# axiom_beta_plugin_module_TE0714_SDI_v0_8.net
KiCad netlist of a schematic drawn in EAGLE
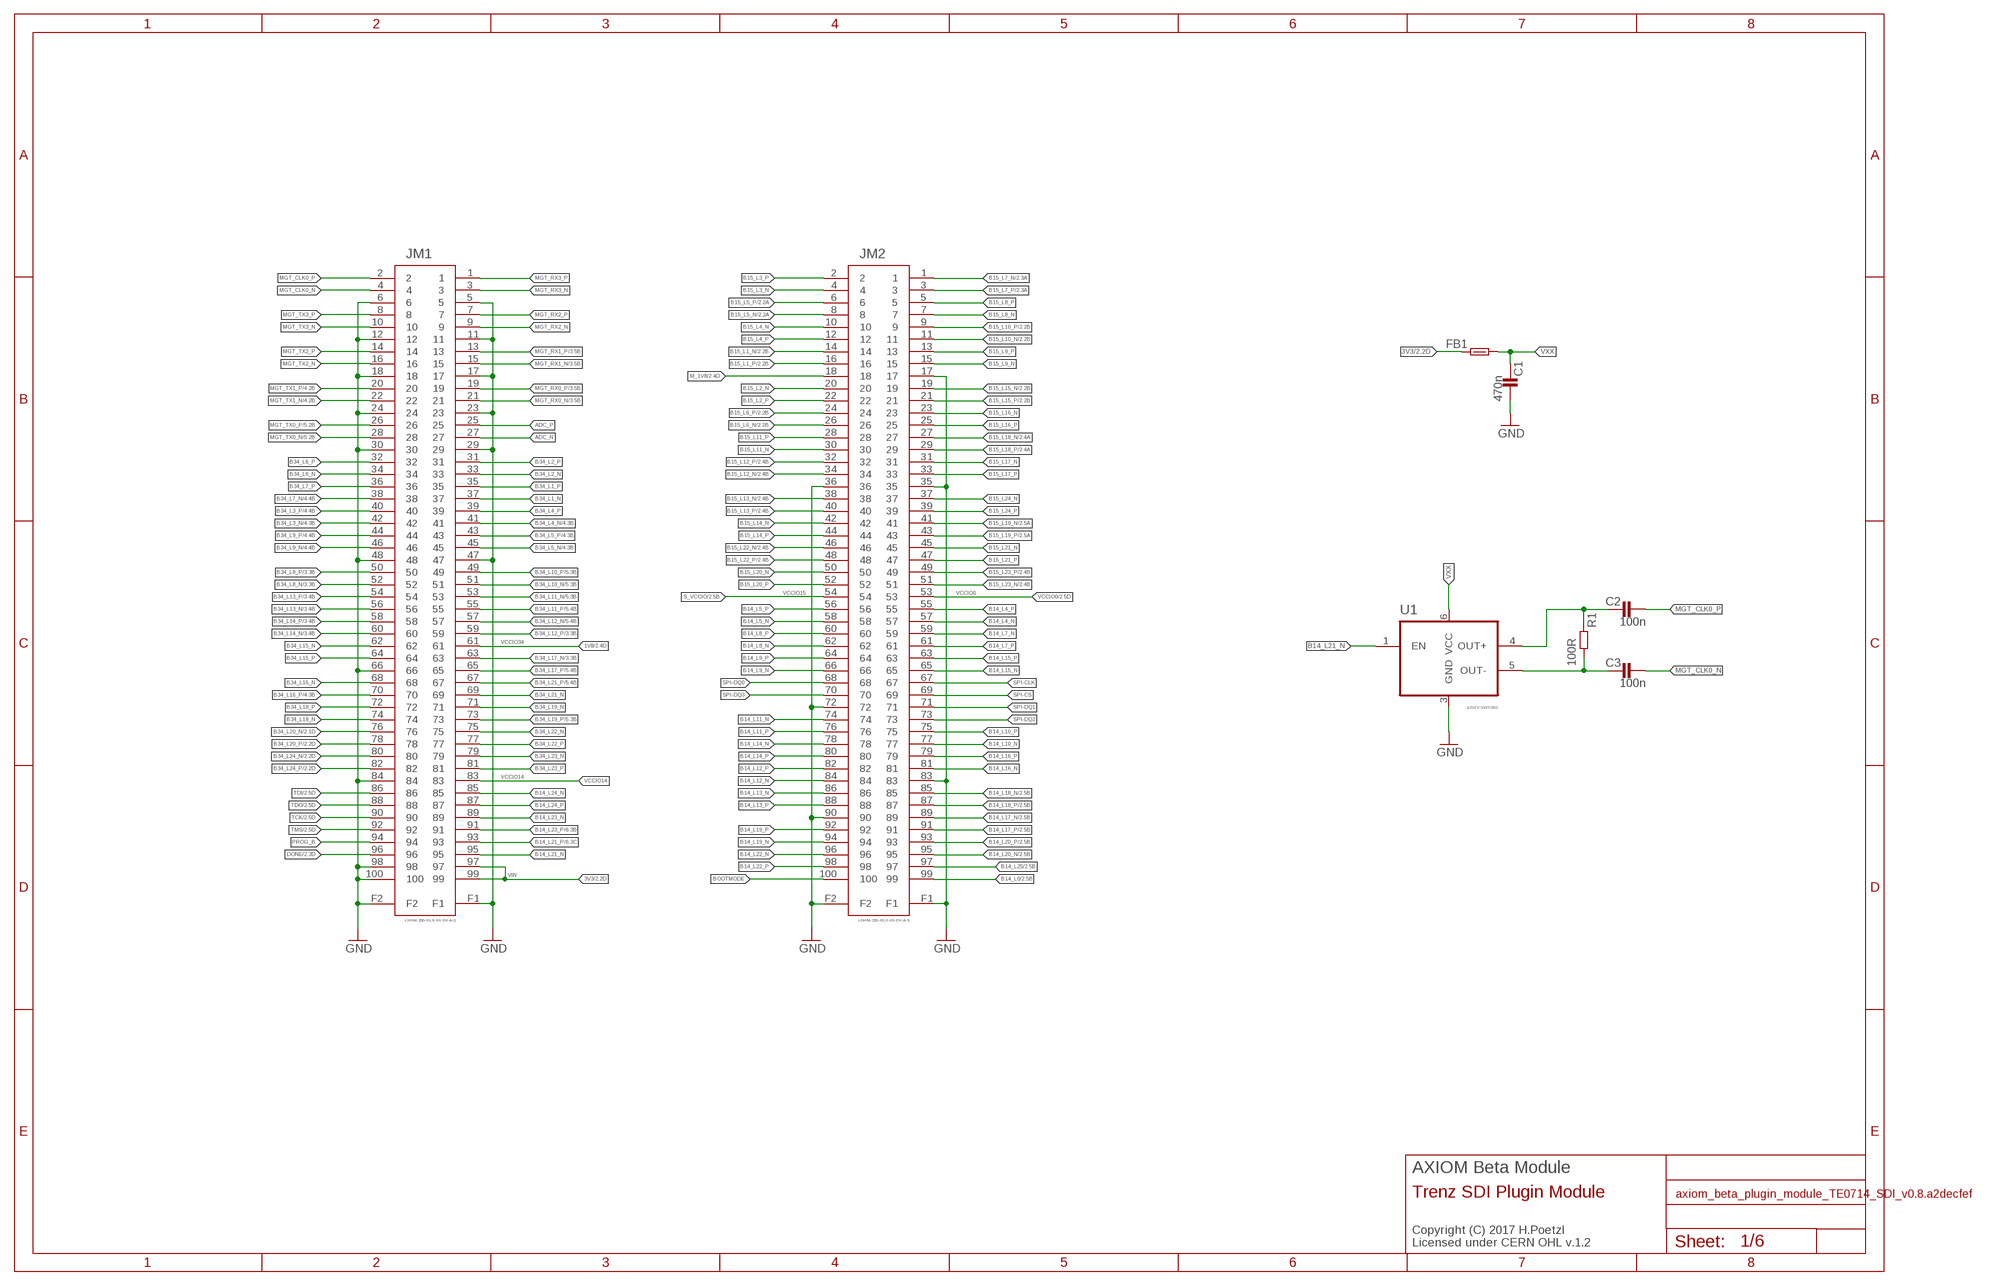
[diagram p0: schematic, sheet 1]
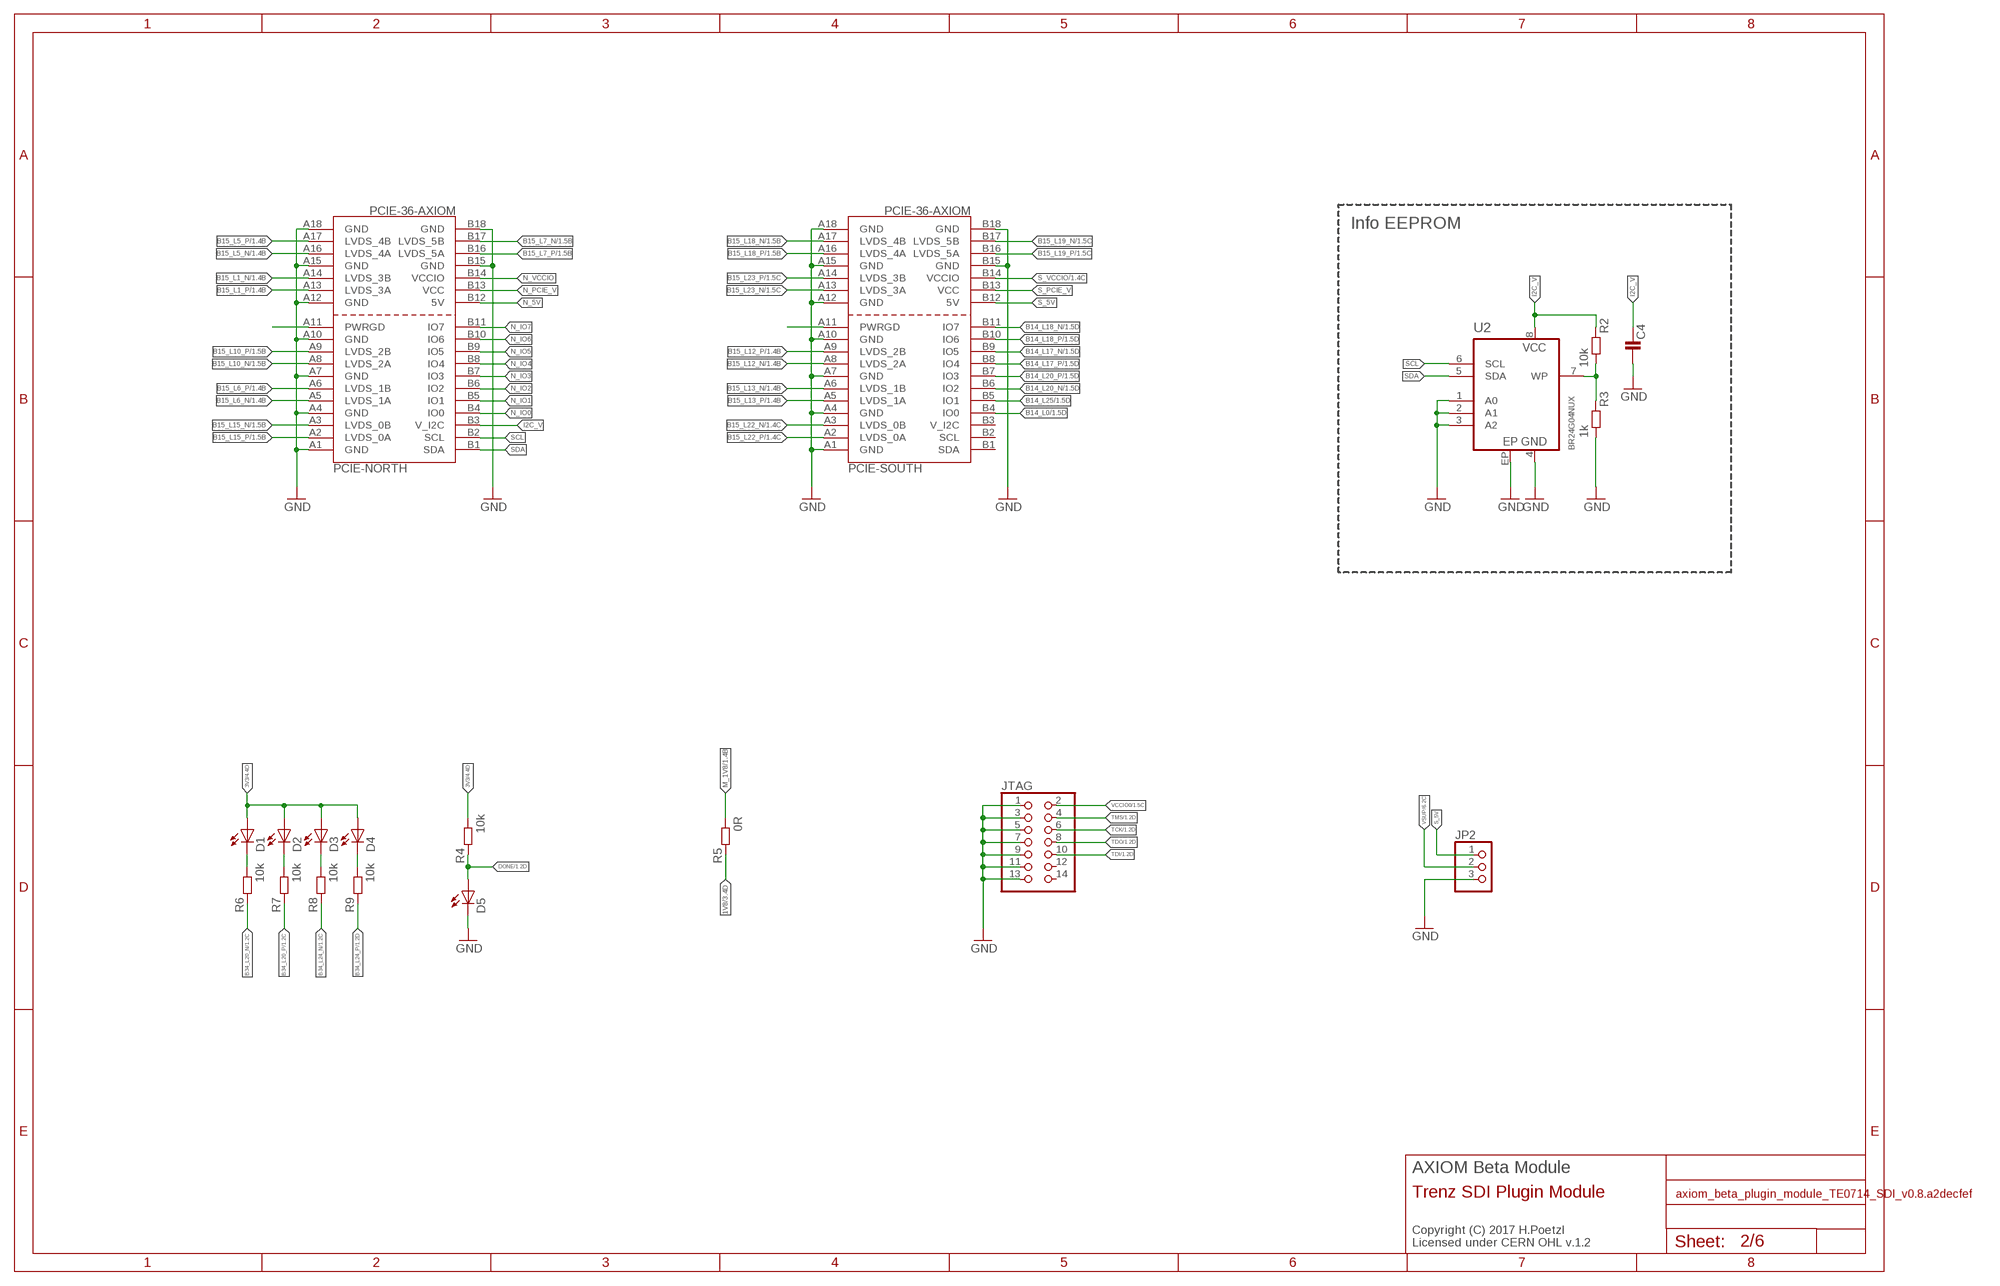
[diagram p1: schematic, sheet 2]
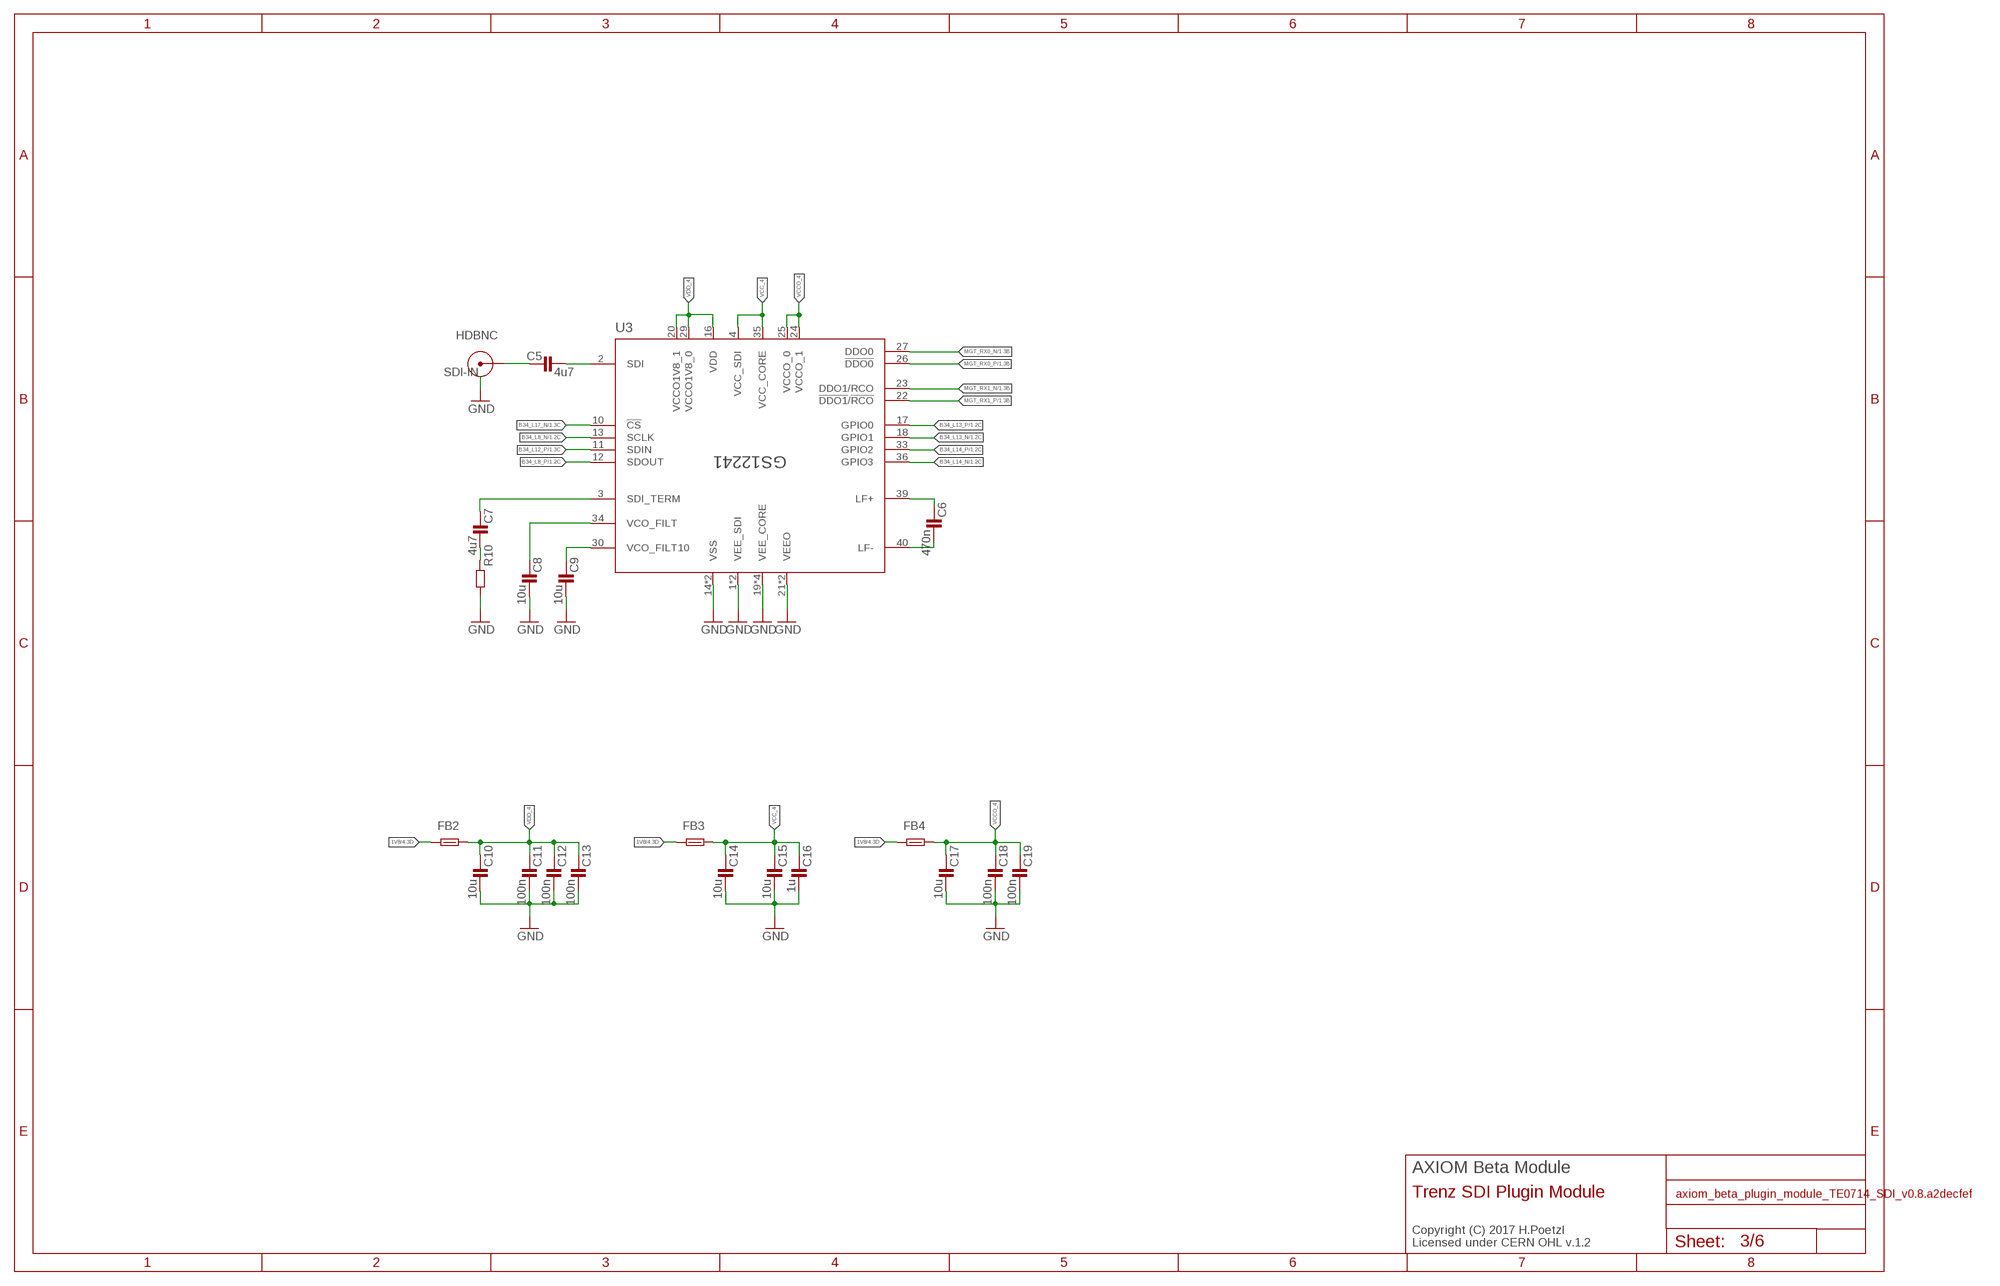
[diagram p2: schematic, sheet 3]
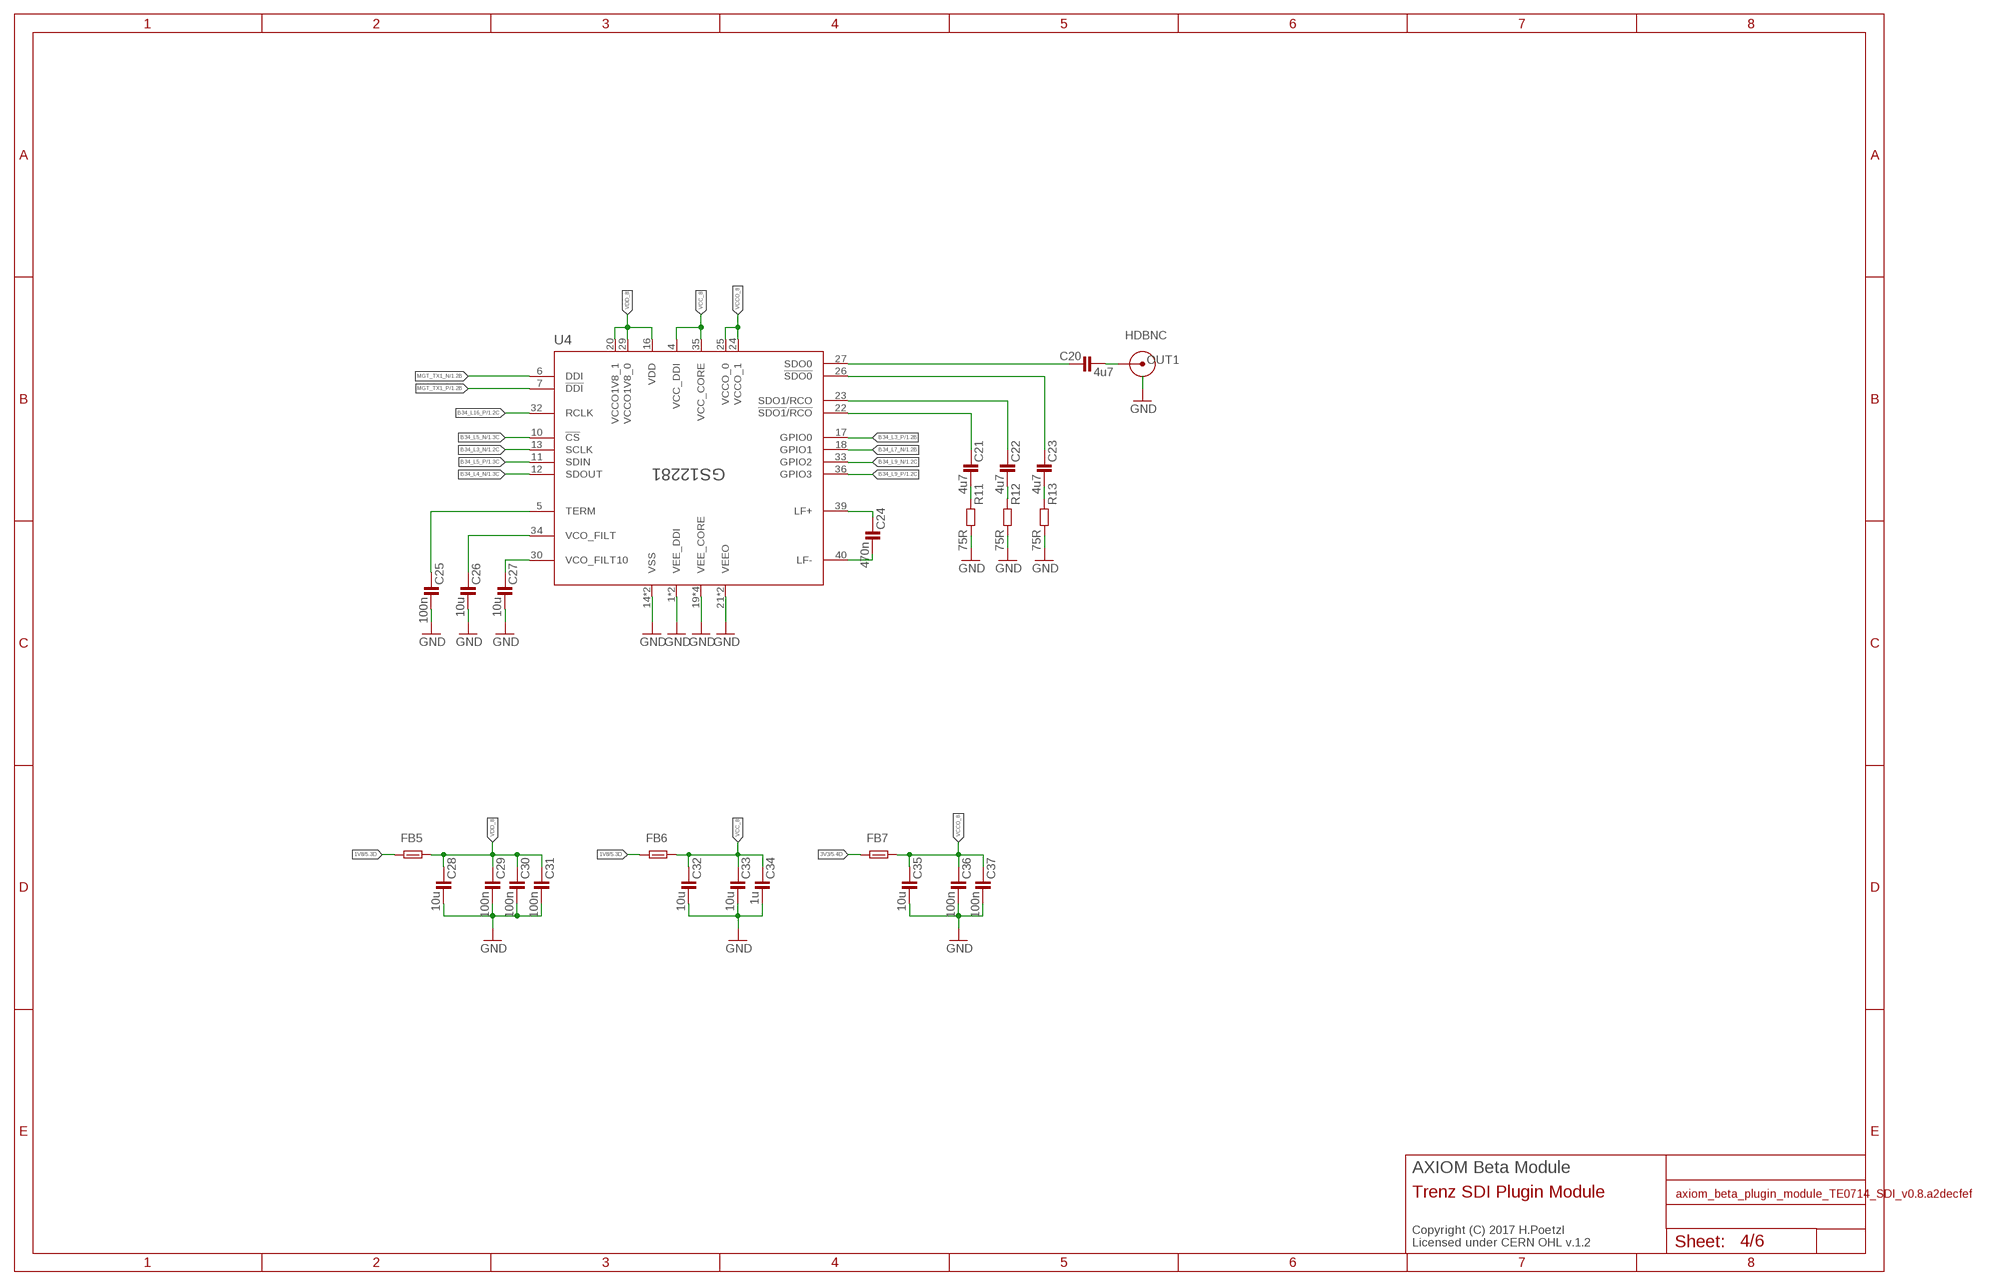
[diagram p3: schematic, sheet 4]
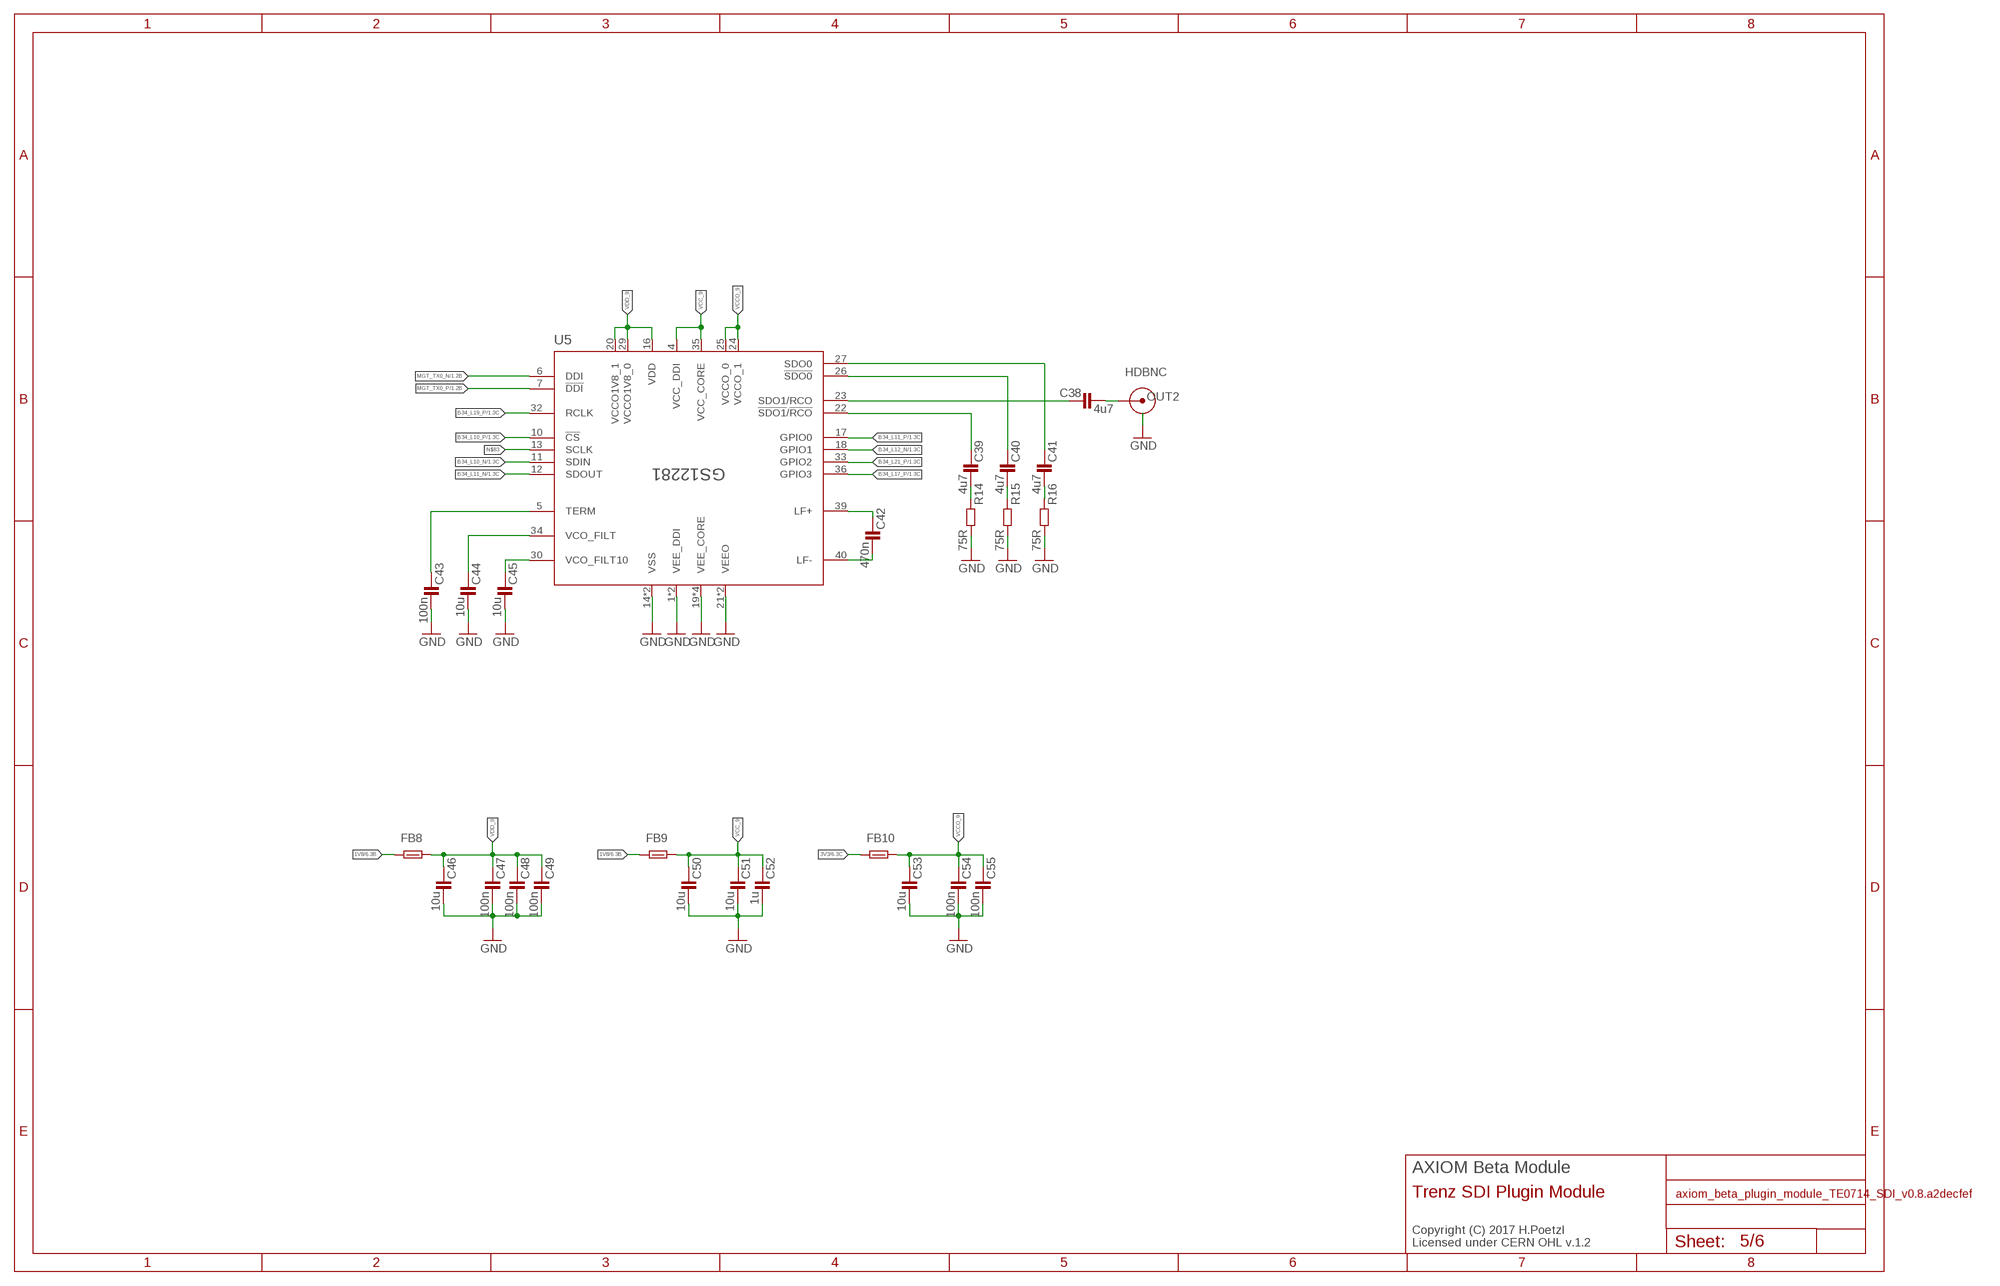
[diagram p4: schematic, sheet 5]
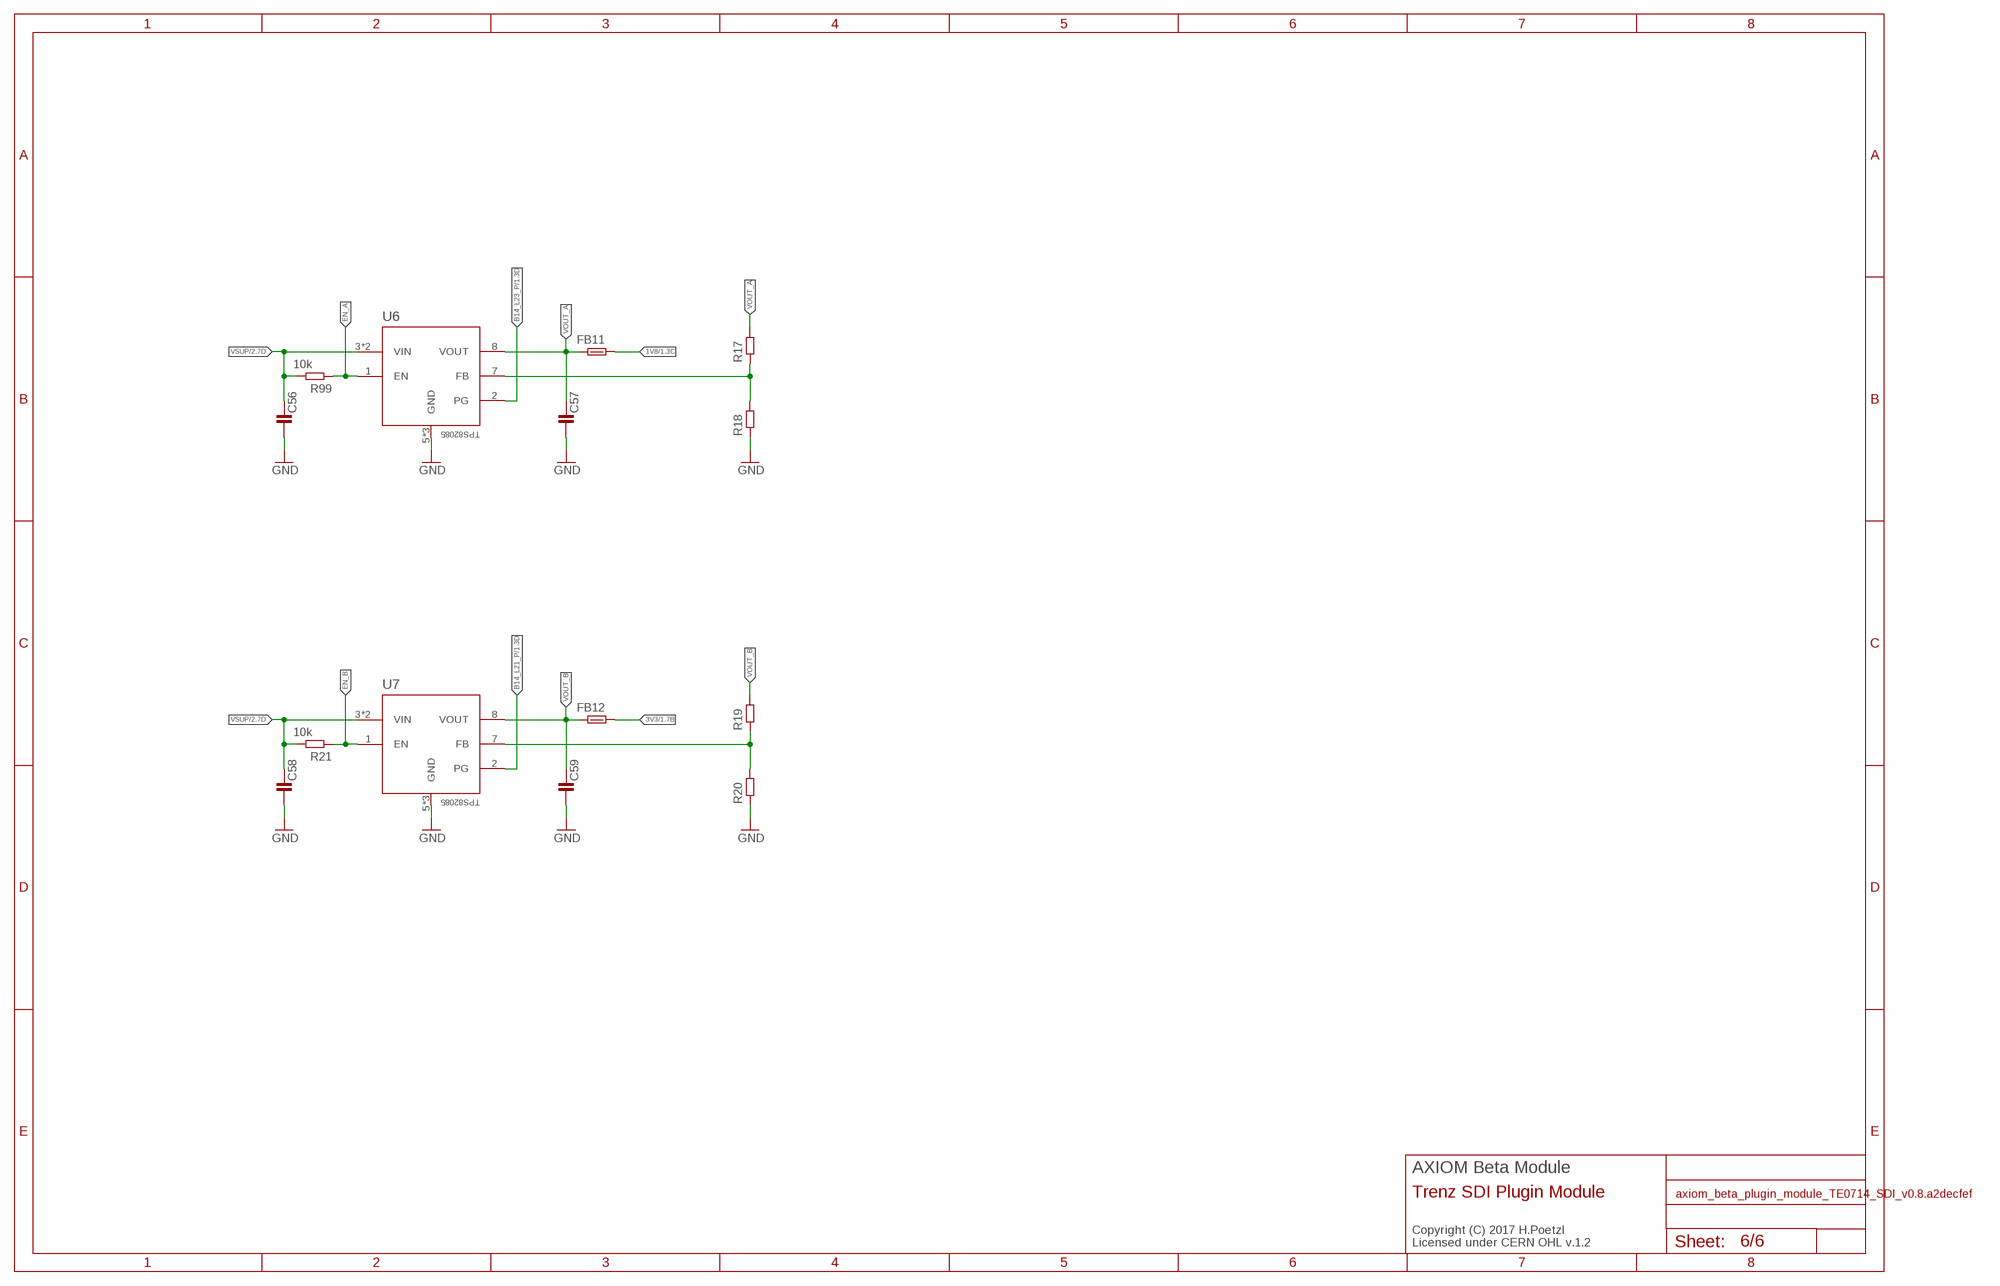
[diagram p5: schematic, sheet 6]

(export (version "E")
  (design (tool "Eeschema 10.0.6"))
  (components
    (comp (ref "C1")
      (value "470n")
      (footprint "eagle-import:0402-C")
      (libsource (lib "eagle-import") (part "C0402-C"))
    )
    (comp (ref "C2")
      (value "100n")
      (footprint "eagle-import:0201-C")
      (libsource (lib "eagle-import") (part "C0201-C"))
    )
    (comp (ref "C3")
      (value "100n")
      (footprint "eagle-import:0201-C")
      (libsource (lib "eagle-import") (part "C0201-C"))
    )
    (comp (ref "FB1")
      (value "FB0402-C")
      (footprint "eagle-import:0402-C")
      (libsource (lib "eagle-import") (part "FB0402-C"))
    )
    (comp (ref "JM1")
      (value "LSHM-150-XX.X-XX-DV-A-S")
      (footprint "eagle-import:LSHM-150-XX.X-XX-DV-A-S")
      (libsource (lib "eagle-import") (part "LSHM-150-XX.X-XX-DV-A-S"))
    )
    (comp (ref "JM2")
      (value "LSHM-150-XX.X-XX-DV-A-S")
      (footprint "eagle-import:LSHM-150-XX.X-XX-DV-A-S")
      (libsource (lib "eagle-import") (part "LSHM-150-XX.X-XX-DV-A-S"))
    )
    (comp (ref "R1")
      (value "100R")
      (footprint "eagle-import:0201-C")
      (libsource (lib "eagle-import") (part "R0201-C"))
    )
    (comp (ref "U1")
      (value "DSC11XX-3.2X2.5")
      (footprint "eagle-import:3.2X2.5")
      (libsource (lib "eagle-import") (part "DSC11XX-3.2X2.5"))
    )
    (comp (ref "C5")
      (value "4u7")
      (footprint "eagle-import:0402-C")
      (libsource (lib "eagle-import") (part "C0402-C"))
    )
    (comp (ref "C6")
      (value "470n")
      (footprint "eagle-import:0201-C")
      (libsource (lib "eagle-import") (part "C0201-C"))
    )
    (comp (ref "C7")
      (value "4u7")
      (footprint "eagle-import:0402-C")
      (libsource (lib "eagle-import") (part "C0402-C"))
    )
    (comp (ref "C8")
      (value "10u")
      (footprint "eagle-import:0201-C")
      (libsource (lib "eagle-import") (part "C0201-C"))
    )
    (comp (ref "C9")
      (value "10u")
      (footprint "eagle-import:0402-C")
      (libsource (lib "eagle-import") (part "C0402-C"))
    )
    (comp (ref "C10")
      (value "10u")
      (footprint "eagle-import:0402-C")
      (libsource (lib "eagle-import") (part "C0402-C"))
    )
    (comp (ref "C11")
      (value "100n")
      (footprint "eagle-import:0201-C")
      (libsource (lib "eagle-import") (part "C0201-C"))
    )
    (comp (ref "C12")
      (value "100n")
      (footprint "eagle-import:0201-C")
      (libsource (lib "eagle-import") (part "C0201-C"))
    )
    (comp (ref "C13")
      (value "100n")
      (footprint "eagle-import:0201-C")
      (libsource (lib "eagle-import") (part "C0201-C"))
    )
    (comp (ref "C14")
      (value "10u")
      (footprint "eagle-import:0402-C")
      (libsource (lib "eagle-import") (part "C0402-C"))
    )
    (comp (ref "C15")
      (value "10u")
      (footprint "eagle-import:0402-C")
      (libsource (lib "eagle-import") (part "C0402-C"))
    )
    (comp (ref "C16")
      (value "1u")
      (footprint "eagle-import:0201-C")
      (libsource (lib "eagle-import") (part "C0201-C"))
    )
    (comp (ref "C17")
      (value "10u")
      (footprint "eagle-import:0402-C")
      (libsource (lib "eagle-import") (part "C0402-C"))
    )
    (comp (ref "C18")
      (value "100n")
      (footprint "eagle-import:0201-C")
      (libsource (lib "eagle-import") (part "C0201-C"))
    )
    (comp (ref "C19")
      (value "100n")
      (footprint "eagle-import:0201-C")
      (libsource (lib "eagle-import") (part "C0201-C"))
    )
    (comp (ref "FB2")
      (value "FB0402-C")
      (footprint "eagle-import:0402-C")
      (libsource (lib "eagle-import") (part "FB0402-C"))
    )
    (comp (ref "FB3")
      (value "FB0402-C")
      (footprint "eagle-import:0402-C")
      (libsource (lib "eagle-import") (part "FB0402-C"))
    )
    (comp (ref "FB4")
      (value "FB0402-C")
      (footprint "eagle-import:0402-C")
      (libsource (lib "eagle-import") (part "FB0402-C"))
    )
    (comp (ref "R10")
      (value "R0201-C")
      (footprint "eagle-import:0201-C")
      (libsource (lib "eagle-import") (part "R0201-C"))
    )
    (comp (ref "SDI-IN")
      (value "HDBNC")
      (footprint "eagle-import:HDBNC_EDGE_2SIDE")
      (libsource (lib "eagle-import") (part "HDBNC"))
    )
    (comp (ref "U3")
      (value "GS12241")
      (footprint "eagle-import:UQFN40P600X400X100-41N")
      (libsource (lib "eagle-import") (part "GS12241"))
    )
    (comp (ref "C4")
      (value "C0402-B")
      (footprint "eagle-import:0402-B")
      (libsource (lib "eagle-import") (part "C0402-B"))
    )
    (comp (ref "D1")
      (value "LED")
      (footprint "eagle-import:CHIPLED_0603")
      (libsource (lib "eagle-import") (part "LED"))
    )
    (comp (ref "D2")
      (value "LED")
      (footprint "eagle-import:CHIPLED_0603")
      (libsource (lib "eagle-import") (part "LED"))
    )
    (comp (ref "D3")
      (value "LED")
      (footprint "eagle-import:CHIPLED_0603")
      (libsource (lib "eagle-import") (part "LED"))
    )
    (comp (ref "D4")
      (value "LED")
      (footprint "eagle-import:CHIPLED_0603")
      (libsource (lib "eagle-import") (part "LED"))
    )
    (comp (ref "D5")
      (value "LED")
      (footprint "eagle-import:CHIPLED_0603")
      (libsource (lib "eagle-import") (part "LED"))
    )
    (comp (ref "JP2")
      (value "PINHD-1X03_2.54-90°-S")
      (footprint "eagle-import:1X03_90-S")
      (libsource (lib "eagle-import") (part "PINHD-1X03_2.54-90°-S"))
    )
    (comp (ref "JTAG")
      (value "PINHD-2X07_2.00")
      (footprint "eagle-import:2X07M")
      (libsource (lib "eagle-import") (part "PINHD-2X07_2.00"))
    )
    (comp (ref "PCIE-NORTH")
      (value "PCIE-36-AXIOM")
      (footprint "eagle-import:PCIE-36-AXIOM")
      (libsource (lib "eagle-import") (part "PCIE-36-AXIOM"))
    )
    (comp (ref "PCIE-SOUTH")
      (value "PCIE-36-AXIOM")
      (footprint "eagle-import:PCIE-36-AXIOM")
      (libsource (lib "eagle-import") (part "PCIE-36-AXIOM"))
    )
    (comp (ref "R2")
      (value "10k")
      (footprint "eagle-import:0402-B")
      (libsource (lib "eagle-import") (part "R0402-B"))
    )
    (comp (ref "R3")
      (value "1k")
      (footprint "eagle-import:0402-B")
      (libsource (lib "eagle-import") (part "R0402-B"))
    )
    (comp (ref "R4")
      (value "10k")
      (footprint "eagle-import:0402-C")
      (libsource (lib "eagle-import") (part "R0402-C"))
    )
    (comp (ref "R5")
      (value "0R")
      (footprint "eagle-import:0402-C")
      (libsource (lib "eagle-import") (part "R0402-C"))
    )
    (comp (ref "R6")
      (value "10k")
      (footprint "eagle-import:0402-C")
      (libsource (lib "eagle-import") (part "R0402-C"))
    )
    (comp (ref "R7")
      (value "10k")
      (footprint "eagle-import:0402-C")
      (libsource (lib "eagle-import") (part "R0402-C"))
    )
    (comp (ref "R8")
      (value "10k")
      (footprint "eagle-import:0402-C")
      (libsource (lib "eagle-import") (part "R0402-C"))
    )
    (comp (ref "R9")
      (value "10k")
      (footprint "eagle-import:0402-C")
      (libsource (lib "eagle-import") (part "R0402-C"))
    )
    (comp (ref "U2")
      (value "BR24G04NUX")
      (footprint "eagle-import:DFN200X300X100-9N")
      (libsource (lib "eagle-import") (part "BR24G04NUX"))
    )
    (comp (ref "C56")
      (value "C0603-C")
      (footprint "eagle-import:0603-C")
      (libsource (lib "eagle-import") (part "C0603-C"))
    )
    (comp (ref "C57")
      (value "C0603-C")
      (footprint "eagle-import:0603-C")
      (libsource (lib "eagle-import") (part "C0603-C"))
    )
    (comp (ref "C58")
      (value "C0603-C")
      (footprint "eagle-import:0603-C")
      (libsource (lib "eagle-import") (part "C0603-C"))
    )
    (comp (ref "C59")
      (value "C0603-C")
      (footprint "eagle-import:0603-C")
      (libsource (lib "eagle-import") (part "C0603-C"))
    )
    (comp (ref "FB11")
      (value "FB0603-C")
      (footprint "eagle-import:0603-C")
      (libsource (lib "eagle-import") (part "FB0603-C"))
    )
    (comp (ref "FB12")
      (value "FB0603-C")
      (footprint "eagle-import:0603-C")
      (libsource (lib "eagle-import") (part "FB0603-C"))
    )
    (comp (ref "R17")
      (value "R0201-C")
      (footprint "eagle-import:0201-C")
      (libsource (lib "eagle-import") (part "R0201-C"))
    )
    (comp (ref "R18")
      (value "R0201-C")
      (footprint "eagle-import:0201-C")
      (libsource (lib "eagle-import") (part "R0201-C"))
    )
    (comp (ref "R19")
      (value "R0201-C")
      (footprint "eagle-import:0201-C")
      (libsource (lib "eagle-import") (part "R0201-C"))
    )
    (comp (ref "R20")
      (value "R0201-C")
      (footprint "eagle-import:0201-C")
      (libsource (lib "eagle-import") (part "R0201-C"))
    )
    (comp (ref "R21")
      (value "10k")
      (footprint "eagle-import:0201-C")
      (libsource (lib "eagle-import") (part "R0201-C"))
    )
    (comp (ref "R99")
      (value "10k")
      (footprint "eagle-import:0201-C")
      (libsource (lib "eagle-import") (part "R0201-C"))
    )
    (comp (ref "U6")
      (value "TPS82085")
      (footprint "eagle-import:MICROSIP")
      (libsource (lib "eagle-import") (part "TPS82085"))
    )
    (comp (ref "U7")
      (value "TPS82085")
      (footprint "eagle-import:MICROSIP")
      (libsource (lib "eagle-import") (part "TPS82085"))
    )
    (comp (ref "C20")
      (value "4u7")
      (footprint "eagle-import:0402-C")
      (libsource (lib "eagle-import") (part "C0402-C"))
    )
    (comp (ref "C21")
      (value "4u7")
      (footprint "eagle-import:0402-C")
      (libsource (lib "eagle-import") (part "C0402-C"))
    )
    (comp (ref "C22")
      (value "4u7")
      (footprint "eagle-import:0402-C")
      (libsource (lib "eagle-import") (part "C0402-C"))
    )
    (comp (ref "C23")
      (value "4u7")
      (footprint "eagle-import:0402-C")
      (libsource (lib "eagle-import") (part "C0402-C"))
    )
    (comp (ref "C24")
      (value "470n")
      (footprint "eagle-import:0201-C")
      (libsource (lib "eagle-import") (part "C0201-C"))
    )
    (comp (ref "C25")
      (value "100n")
      (footprint "eagle-import:0201-C")
      (libsource (lib "eagle-import") (part "C0201-C"))
    )
    (comp (ref "C26")
      (value "10u")
      (footprint "eagle-import:0201-C")
      (libsource (lib "eagle-import") (part "C0201-C"))
    )
    (comp (ref "C27")
      (value "10u")
      (footprint "eagle-import:0402-C")
      (libsource (lib "eagle-import") (part "C0402-C"))
    )
    (comp (ref "C28")
      (value "10u")
      (footprint "eagle-import:0402-C")
      (libsource (lib "eagle-import") (part "C0402-C"))
    )
    (comp (ref "C29")
      (value "100n")
      (footprint "eagle-import:0201-C")
      (libsource (lib "eagle-import") (part "C0201-C"))
    )
    (comp (ref "C30")
      (value "100n")
      (footprint "eagle-import:0201-C")
      (libsource (lib "eagle-import") (part "C0201-C"))
    )
    (comp (ref "C31")
      (value "100n")
      (footprint "eagle-import:0201-C")
      (libsource (lib "eagle-import") (part "C0201-C"))
    )
    (comp (ref "C32")
      (value "10u")
      (footprint "eagle-import:0402-C")
      (libsource (lib "eagle-import") (part "C0402-C"))
    )
    (comp (ref "C33")
      (value "10u")
      (footprint "eagle-import:0402-C")
      (libsource (lib "eagle-import") (part "C0402-C"))
    )
    (comp (ref "C34")
      (value "1u")
      (footprint "eagle-import:0201-C")
      (libsource (lib "eagle-import") (part "C0201-C"))
    )
    (comp (ref "C35")
      (value "10u")
      (footprint "eagle-import:0402-C")
      (libsource (lib "eagle-import") (part "C0402-C"))
    )
    (comp (ref "C36")
      (value "100n")
      (footprint "eagle-import:0201-C")
      (libsource (lib "eagle-import") (part "C0201-C"))
    )
    (comp (ref "C37")
      (value "100n")
      (footprint "eagle-import:0201-C")
      (libsource (lib "eagle-import") (part "C0201-C"))
    )
    (comp (ref "FB5")
      (value "FB0402-C")
      (footprint "eagle-import:0402-C")
      (libsource (lib "eagle-import") (part "FB0402-C"))
    )
    (comp (ref "FB6")
      (value "FB0402-C")
      (footprint "eagle-import:0402-C")
      (libsource (lib "eagle-import") (part "FB0402-C"))
    )
    (comp (ref "FB7")
      (value "FB0402-C")
      (footprint "eagle-import:0402-C")
      (libsource (lib "eagle-import") (part "FB0402-C"))
    )
    (comp (ref "OUT1")
      (value "HDBNC")
      (footprint "eagle-import:HDBNC_EDGE_2SIDE")
      (libsource (lib "eagle-import") (part "HDBNC"))
    )
    (comp (ref "R11")
      (value "75R")
      (footprint "eagle-import:0201-C")
      (libsource (lib "eagle-import") (part "R0201-C"))
    )
    (comp (ref "R12")
      (value "75R")
      (footprint "eagle-import:0201-C")
      (libsource (lib "eagle-import") (part "R0201-C"))
    )
    (comp (ref "R13")
      (value "75R")
      (footprint "eagle-import:0201-C")
      (libsource (lib "eagle-import") (part "R0201-C"))
    )
    (comp (ref "U4")
      (value "GS12281")
      (footprint "eagle-import:UQFN40P600X400X100-41N")
      (libsource (lib "eagle-import") (part "GS12281"))
    )
    (comp (ref "C38")
      (value "4u7")
      (footprint "eagle-import:0402-C")
      (libsource (lib "eagle-import") (part "C0402-C"))
    )
    (comp (ref "C39")
      (value "4u7")
      (footprint "eagle-import:0402-C")
      (libsource (lib "eagle-import") (part "C0402-C"))
    )
    (comp (ref "C40")
      (value "4u7")
      (footprint "eagle-import:0402-C")
      (libsource (lib "eagle-import") (part "C0402-C"))
    )
    (comp (ref "C41")
      (value "4u7")
      (footprint "eagle-import:0402-C")
      (libsource (lib "eagle-import") (part "C0402-C"))
    )
    (comp (ref "C42")
      (value "470n")
      (footprint "eagle-import:0201-C")
      (libsource (lib "eagle-import") (part "C0201-C"))
    )
    (comp (ref "C43")
      (value "100n")
      (footprint "eagle-import:0201-C")
      (libsource (lib "eagle-import") (part "C0201-C"))
    )
    (comp (ref "C44")
      (value "10u")
      (footprint "eagle-import:0402-C")
      (libsource (lib "eagle-import") (part "C0402-C"))
    )
    (comp (ref "C45")
      (value "10u")
      (footprint "eagle-import:0402-C")
      (libsource (lib "eagle-import") (part "C0402-C"))
    )
    (comp (ref "C46")
      (value "10u")
      (footprint "eagle-import:0402-C")
      (libsource (lib "eagle-import") (part "C0402-C"))
    )
    (comp (ref "C47")
      (value "100n")
      (footprint "eagle-import:0201-C")
      (libsource (lib "eagle-import") (part "C0201-C"))
    )
    (comp (ref "C48")
      (value "100n")
      (footprint "eagle-import:0201-C")
      (libsource (lib "eagle-import") (part "C0201-C"))
    )
    (comp (ref "C49")
      (value "100n")
      (footprint "eagle-import:0201-C")
      (libsource (lib "eagle-import") (part "C0201-C"))
    )
    (comp (ref "C50")
      (value "10u")
      (footprint "eagle-import:0402-C")
      (libsource (lib "eagle-import") (part "C0402-C"))
    )
    (comp (ref "C51")
      (value "10u")
      (footprint "eagle-import:0402-C")
      (libsource (lib "eagle-import") (part "C0402-C"))
    )
    (comp (ref "C52")
      (value "1u")
      (footprint "eagle-import:0201-C")
      (libsource (lib "eagle-import") (part "C0201-C"))
    )
    (comp (ref "C53")
      (value "10u")
      (footprint "eagle-import:0402-C")
      (libsource (lib "eagle-import") (part "C0402-C"))
    )
    (comp (ref "C54")
      (value "100n")
      (footprint "eagle-import:0201-C")
      (libsource (lib "eagle-import") (part "C0201-C"))
    )
    (comp (ref "C55")
      (value "100n")
      (footprint "eagle-import:0201-C")
      (libsource (lib "eagle-import") (part "C0201-C"))
    )
    (comp (ref "FB8")
      (value "FB0402-C")
      (footprint "eagle-import:0402-C")
      (libsource (lib "eagle-import") (part "FB0402-C"))
    )
    (comp (ref "FB9")
      (value "FB0402-C")
      (footprint "eagle-import:0402-C")
      (libsource (lib "eagle-import") (part "FB0402-C"))
    )
    (comp (ref "FB10")
      (value "FB0402-C")
      (footprint "eagle-import:0402-C")
      (libsource (lib "eagle-import") (part "FB0402-C"))
    )
    (comp (ref "OUT2")
      (value "HDBNC")
      (footprint "eagle-import:HDBNC_EDGE_2SIDE")
      (libsource (lib "eagle-import") (part "HDBNC"))
    )
    (comp (ref "R14")
      (value "75R")
      (footprint "eagle-import:0201-C")
      (libsource (lib "eagle-import") (part "R0201-C"))
    )
    (comp (ref "R15")
      (value "75R")
      (footprint "eagle-import:0201-C")
      (libsource (lib "eagle-import") (part "R0201-C"))
    )
    (comp (ref "R16")
      (value "75R")
      (footprint "eagle-import:0201-C")
      (libsource (lib "eagle-import") (part "R0201-C"))
    )
    (comp (ref "U5")
      (value "GS12281")
      (footprint "eagle-import:UQFN40P600X400X100-41N")
      (libsource (lib "eagle-import") (part "GS12281"))
    )
  )
  (nets
    (net (code "1") (name "1V8") (class "Default")
      (node (ref "FB11") (pin "2") (pinfunction "2_2") (pintype "passive"))
      (node (ref "FB2") (pin "1") (pinfunction "1_1") (pintype "passive"))
      (node (ref "FB3") (pin "1") (pinfunction "1_1") (pintype "passive"))
      (node (ref "FB4") (pin "1") (pinfunction "1_1") (pintype "passive"))
      (node (ref "FB5") (pin "1") (pinfunction "1_1") (pintype "passive"))
      (node (ref "FB6") (pin "1") (pinfunction "1_1") (pintype "passive"))
      (node (ref "FB8") (pin "1") (pinfunction "1_1") (pintype "passive"))
      (node (ref "FB9") (pin "1") (pinfunction "1_1") (pintype "passive"))
      (node (ref "JM1") (pin "61") (pinfunction "61_61") (pintype "bidirectional"))
      (node (ref "R5") (pin "1") (pinfunction "1_1") (pintype "passive"))
    )
    (net (code "2") (name "3V3") (class "Default")
      (node (ref "D1") (pin "A") (pinfunction "A_A") (pintype "passive"))
      (node (ref "D2") (pin "A") (pinfunction "A_A") (pintype "passive"))
      (node (ref "D3") (pin "A") (pinfunction "A_A") (pintype "passive"))
      (node (ref "D4") (pin "A") (pinfunction "A_A") (pintype "passive"))
      (node (ref "FB1") (pin "1") (pinfunction "1_1") (pintype "passive"))
      (node (ref "FB10") (pin "1") (pinfunction "1_1") (pintype "passive"))
      (node (ref "FB12") (pin "2") (pinfunction "2_2") (pintype "passive"))
      (node (ref "FB7") (pin "1") (pinfunction "1_1") (pintype "passive"))
      (node (ref "JM1") (pin "97") (pinfunction "97_97") (pintype "bidirectional"))
      (node (ref "JM1") (pin "99") (pinfunction "99_99") (pintype "bidirectional"))
      (node (ref "R4") (pin "2") (pinfunction "2_2") (pintype "passive"))
    )
    (net (code "3") (name "ADC_N") (class "Default")
      (node (ref "JM1") (pin "27") (pinfunction "27_27") (pintype "bidirectional"))
    )
    (net (code "4") (name "ADC_P") (class "Default")
      (node (ref "JM1") (pin "25") (pinfunction "25_25") (pintype "bidirectional"))
    )
    (net (code "5") (name "B14_L0") (class "Default")
      (node (ref "JM2") (pin "99") (pinfunction "99_99") (pintype "bidirectional"))
      (node (ref "PCIE-SOUTH") (pin "B4") (pinfunction "IO0_B4") (pintype "passive"))
    )
    (net (code "6") (name "B14_L4_N") (class "Default")
      (node (ref "JM2") (pin "57") (pinfunction "57_57") (pintype "bidirectional"))
    )
    (net (code "7") (name "B14_L4_P") (class "Default")
      (node (ref "JM2") (pin "55") (pinfunction "55_55") (pintype "bidirectional"))
    )
    (net (code "8") (name "B14_L5_N") (class "Default")
      (node (ref "JM2") (pin "58") (pinfunction "58_58") (pintype "bidirectional"))
    )
    (net (code "9") (name "B14_L5_P") (class "Default")
      (node (ref "JM2") (pin "56") (pinfunction "56_56") (pintype "bidirectional"))
    )
    (net (code "10") (name "B14_L7_N") (class "Default")
      (node (ref "JM2") (pin "59") (pinfunction "59_59") (pintype "bidirectional"))
    )
    (net (code "11") (name "B14_L7_P") (class "Default")
      (node (ref "JM2") (pin "61") (pinfunction "61_61") (pintype "bidirectional"))
    )
    (net (code "12") (name "B14_L8_N") (class "Default")
      (node (ref "JM2") (pin "62") (pinfunction "62_62") (pintype "bidirectional"))
    )
    (net (code "13") (name "B14_L8_P") (class "Default")
      (node (ref "JM2") (pin "60") (pinfunction "60_60") (pintype "bidirectional"))
    )
    (net (code "14") (name "B14_L9_N") (class "Default")
      (node (ref "JM2") (pin "66") (pinfunction "66_66") (pintype "bidirectional"))
    )
    (net (code "15") (name "B14_L9_P") (class "Default")
      (node (ref "JM2") (pin "64") (pinfunction "64_64") (pintype "bidirectional"))
    )
    (net (code "16") (name "B14_L10_N") (class "Default")
      (node (ref "JM2") (pin "77") (pinfunction "77_77") (pintype "bidirectional"))
    )
    (net (code "17") (name "B14_L10_P") (class "Default")
      (node (ref "JM2") (pin "75") (pinfunction "75_75") (pintype "bidirectional"))
    )
    (net (code "18") (name "B14_L11_N") (class "Default")
      (node (ref "JM2") (pin "74") (pinfunction "74_74") (pintype "bidirectional"))
    )
    (net (code "19") (name "B14_L11_P") (class "Default")
      (node (ref "JM2") (pin "76") (pinfunction "76_76") (pintype "bidirectional"))
    )
    (net (code "20") (name "B14_L12_N") (class "Default")
      (node (ref "JM2") (pin "84") (pinfunction "84_84") (pintype "bidirectional"))
    )
    (net (code "21") (name "B14_L12_P") (class "Default")
      (node (ref "JM2") (pin "82") (pinfunction "82_82") (pintype "bidirectional"))
    )
    (net (code "22") (name "B14_L13_N") (class "Default")
      (node (ref "JM2") (pin "86") (pinfunction "86_86") (pintype "bidirectional"))
    )
    (net (code "23") (name "B14_L13_P") (class "Default")
      (node (ref "JM2") (pin "88") (pinfunction "88_88") (pintype "bidirectional"))
    )
    (net (code "24") (name "B14_L14_N") (class "Default")
      (node (ref "JM2") (pin "78") (pinfunction "78_78") (pintype "bidirectional"))
    )
    (net (code "25") (name "B14_L14_P") (class "Default")
      (node (ref "JM2") (pin "80") (pinfunction "80_80") (pintype "bidirectional"))
    )
    (net (code "26") (name "B14_L15_N") (class "Default")
      (node (ref "JM2") (pin "65") (pinfunction "65_65") (pintype "bidirectional"))
    )
    (net (code "27") (name "B14_L15_P") (class "Default")
      (node (ref "JM2") (pin "63") (pinfunction "63_63") (pintype "bidirectional"))
    )
    (net (code "28") (name "B14_L16_N") (class "Default")
      (node (ref "JM2") (pin "81") (pinfunction "81_81") (pintype "bidirectional"))
    )
    (net (code "29") (name "B14_L16_P") (class "Default")
      (node (ref "JM2") (pin "79") (pinfunction "79_79") (pintype "bidirectional"))
    )
    (net (code "30") (name "B14_L17_N") (class "Default")
      (node (ref "JM2") (pin "89") (pinfunction "89_89") (pintype "bidirectional"))
      (node (ref "PCIE-SOUTH") (pin "B9") (pinfunction "IO5_B9") (pintype "passive"))
    )
    (net (code "31") (name "B14_L17_P") (class "Default")
      (node (ref "JM2") (pin "91") (pinfunction "91_91") (pintype "bidirectional"))
      (node (ref "PCIE-SOUTH") (pin "B8") (pinfunction "IO4_B8") (pintype "passive"))
    )
    (net (code "32") (name "B14_L18_N") (class "Default")
      (node (ref "JM2") (pin "85") (pinfunction "85_85") (pintype "bidirectional"))
      (node (ref "PCIE-SOUTH") (pin "B11") (pinfunction "IO7_B11") (pintype "passive"))
    )
    (net (code "33") (name "B14_L18_P") (class "Default")
      (node (ref "JM2") (pin "87") (pinfunction "87_87") (pintype "bidirectional"))
      (node (ref "PCIE-SOUTH") (pin "B10") (pinfunction "IO6_B10") (pintype "passive"))
    )
    (net (code "34") (name "B14_L19_N") (class "Default")
      (node (ref "JM2") (pin "94") (pinfunction "94_94") (pintype "bidirectional"))
    )
    (net (code "35") (name "B14_L19_P") (class "Default")
      (node (ref "JM2") (pin "92") (pinfunction "92_92") (pintype "bidirectional"))
    )
    (net (code "36") (name "B14_L20_N") (class "Default")
      (node (ref "JM2") (pin "95") (pinfunction "95_95") (pintype "bidirectional"))
      (node (ref "PCIE-SOUTH") (pin "B6") (pinfunction "IO2_B6") (pintype "passive"))
    )
    (net (code "37") (name "B14_L20_P") (class "Default")
      (node (ref "JM2") (pin "93") (pinfunction "93_93") (pintype "bidirectional"))
      (node (ref "PCIE-SOUTH") (pin "B7") (pinfunction "IO3_B7") (pintype "passive"))
    )
    (net (code "38") (name "B14_L21_N") (class "Default")
      (node (ref "JM1") (pin "95") (pinfunction "95_95") (pintype "bidirectional"))
      (node (ref "U1") (pin "1") (pinfunction "EN_1") (pintype "input"))
    )
    (net (code "39") (name "B14_L21_P") (class "Default")
      (node (ref "JM1") (pin "93") (pinfunction "93_93") (pintype "bidirectional"))
      (node (ref "U7") (pin "2") (pinfunction "PG_2") (pintype "power_in"))
    )
    (net (code "40") (name "B14_L22_N") (class "Default")
      (node (ref "JM2") (pin "96") (pinfunction "96_96") (pintype "bidirectional"))
    )
    (net (code "41") (name "B14_L22_P") (class "Default")
      (node (ref "JM2") (pin "98") (pinfunction "98_98") (pintype "bidirectional"))
    )
    (net (code "42") (name "B14_L23_N") (class "Default")
      (node (ref "JM1") (pin "89") (pinfunction "89_89") (pintype "bidirectional"))
    )
    (net (code "43") (name "B14_L23_P") (class "Default")
      (node (ref "JM1") (pin "91") (pinfunction "91_91") (pintype "bidirectional"))
      (node (ref "U6") (pin "2") (pinfunction "PG_2") (pintype "power_in"))
    )
    (net (code "44") (name "B14_L24_N") (class "Default")
      (node (ref "JM1") (pin "85") (pinfunction "85_85") (pintype "bidirectional"))
    )
    (net (code "45") (name "B14_L24_P") (class "Default")
      (node (ref "JM1") (pin "87") (pinfunction "87_87") (pintype "bidirectional"))
    )
    (net (code "46") (name "B14_L25") (class "Default")
      (node (ref "JM2") (pin "97") (pinfunction "97_97") (pintype "bidirectional"))
      (node (ref "PCIE-SOUTH") (pin "B5") (pinfunction "IO1_B5") (pintype "passive"))
    )
    (net (code "47") (name "B15_L1_N") (class "Default")
      (node (ref "JM2") (pin "14") (pinfunction "14_14") (pintype "bidirectional"))
      (node (ref "PCIE-NORTH") (pin "A14") (pinfunction "LVDS_3B_A14") (pintype "passive"))
    )
    (net (code "48") (name "B15_L1_P") (class "Default")
      (node (ref "JM2") (pin "16") (pinfunction "16_16") (pintype "bidirectional"))
      (node (ref "PCIE-NORTH") (pin "A13") (pinfunction "LVDS_3A_A13") (pintype "passive"))
    )
    (net (code "49") (name "B15_L2_N") (class "Default")
      (node (ref "JM2") (pin "20") (pinfunction "20_20") (pintype "bidirectional"))
    )
    (net (code "50") (name "B15_L2_P") (class "Default")
      (node (ref "JM2") (pin "22") (pinfunction "22_22") (pintype "bidirectional"))
    )
    (net (code "51") (name "B15_L3_N") (class "Default")
      (node (ref "JM2") (pin "4") (pinfunction "4_4") (pintype "bidirectional"))
    )
    (net (code "52") (name "B15_L3_P") (class "Default")
      (node (ref "JM2") (pin "2") (pinfunction "2_2") (pintype "bidirectional"))
    )
    (net (code "53") (name "B15_L4_N") (class "Default")
      (node (ref "JM2") (pin "10") (pinfunction "10_10") (pintype "bidirectional"))
    )
    (net (code "54") (name "B15_L4_P") (class "Default")
      (node (ref "JM2") (pin "12") (pinfunction "12_12") (pintype "bidirectional"))
    )
    (net (code "55") (name "B15_L5_N") (class "Default")
      (node (ref "JM2") (pin "8") (pinfunction "8_8") (pintype "bidirectional"))
      (node (ref "PCIE-NORTH") (pin "A16") (pinfunction "LVDS_4A_A16") (pintype "passive"))
    )
    (net (code "56") (name "B15_L5_P") (class "Default")
      (node (ref "JM2") (pin "6") (pinfunction "6_6") (pintype "bidirectional"))
      (node (ref "PCIE-NORTH") (pin "A17") (pinfunction "LVDS_4B_A17") (pintype "passive"))
    )
    (net (code "57") (name "B15_L6_N") (class "Default")
      (node (ref "JM2") (pin "26") (pinfunction "26_26") (pintype "bidirectional"))
      (node (ref "PCIE-NORTH") (pin "A5") (pinfunction "LVDS_1A_A5") (pintype "passive"))
    )
    (net (code "58") (name "B15_L6_P") (class "Default")
      (node (ref "JM2") (pin "24") (pinfunction "24_24") (pintype "bidirectional"))
      (node (ref "PCIE-NORTH") (pin "A6") (pinfunction "LVDS_1B_A6") (pintype "passive"))
    )
    (net (code "59") (name "B15_L7_N") (class "Default")
      (node (ref "JM2") (pin "1") (pinfunction "1_1") (pintype "bidirectional"))
      (node (ref "PCIE-NORTH") (pin "B17") (pinfunction "LVDS_5B_B17") (pintype "passive"))
    )
    (net (code "60") (name "B15_L7_P") (class "Default")
      (node (ref "JM2") (pin "3") (pinfunction "3_3") (pintype "bidirectional"))
      (node (ref "PCIE-NORTH") (pin "B16") (pinfunction "LVDS_5A_B16") (pintype "passive"))
    )
    (net (code "61") (name "B15_L8_N") (class "Default")
      (node (ref "JM2") (pin "7") (pinfunction "7_7") (pintype "bidirectional"))
    )
    (net (code "62") (name "B15_L8_P") (class "Default")
      (node (ref "JM2") (pin "5") (pinfunction "5_5") (pintype "bidirectional"))
    )
    (net (code "63") (name "B15_L9_N") (class "Default")
      (node (ref "JM2") (pin "15") (pinfunction "15_15") (pintype "bidirectional"))
    )
    (net (code "64") (name "B15_L9_P") (class "Default")
      (node (ref "JM2") (pin "13") (pinfunction "13_13") (pintype "bidirectional"))
    )
    (net (code "65") (name "B15_L10_N") (class "Default")
      (node (ref "JM2") (pin "11") (pinfunction "11_11") (pintype "bidirectional"))
      (node (ref "PCIE-NORTH") (pin "A8") (pinfunction "LVDS_2A_A8") (pintype "passive"))
    )
    (net (code "66") (name "B15_L10_P") (class "Default")
      (node (ref "JM2") (pin "9") (pinfunction "9_9") (pintype "bidirectional"))
      (node (ref "PCIE-NORTH") (pin "A9") (pinfunction "LVDS_2B_A9") (pintype "passive"))
    )
    (net (code "67") (name "B15_L11_N") (class "Default")
      (node (ref "JM2") (pin "30") (pinfunction "30_30") (pintype "bidirectional"))
    )
    (net (code "68") (name "B15_L11_P") (class "Default")
      (node (ref "JM2") (pin "28") (pinfunction "28_28") (pintype "bidirectional"))
    )
    (net (code "69") (name "B15_L12_N") (class "Default")
      (node (ref "JM2") (pin "34") (pinfunction "34_34") (pintype "bidirectional"))
      (node (ref "PCIE-SOUTH") (pin "A8") (pinfunction "LVDS_2A_A8") (pintype "passive"))
    )
    (net (code "70") (name "B15_L12_P") (class "Default")
      (node (ref "JM2") (pin "32") (pinfunction "32_32") (pintype "bidirectional"))
      (node (ref "PCIE-SOUTH") (pin "A9") (pinfunction "LVDS_2B_A9") (pintype "passive"))
    )
    (net (code "71") (name "B15_L13_N") (class "Default")
      (node (ref "JM2") (pin "38") (pinfunction "38_38") (pintype "bidirectional"))
      (node (ref "PCIE-SOUTH") (pin "A6") (pinfunction "LVDS_1B_A6") (pintype "passive"))
    )
    (net (code "72") (name "B15_L13_P") (class "Default")
      (node (ref "JM2") (pin "40") (pinfunction "40_40") (pintype "bidirectional"))
      (node (ref "PCIE-SOUTH") (pin "A5") (pinfunction "LVDS_1A_A5") (pintype "passive"))
    )
    (net (code "73") (name "B15_L14_N") (class "Default")
      (node (ref "JM2") (pin "42") (pinfunction "42_42") (pintype "bidirectional"))
    )
    (net (code "74") (name "B15_L14_P") (class "Default")
      (node (ref "JM2") (pin "44") (pinfunction "44_44") (pintype "bidirectional"))
    )
    (net (code "75") (name "B15_L15_N") (class "Default")
      (node (ref "JM2") (pin "19") (pinfunction "19_19") (pintype "bidirectional"))
      (node (ref "PCIE-NORTH") (pin "A3") (pinfunction "LVDS_0B_A3") (pintype "passive"))
    )
    (net (code "76") (name "B15_L15_P") (class "Default")
      (node (ref "JM2") (pin "21") (pinfunction "21_21") (pintype "bidirectional"))
      (node (ref "PCIE-NORTH") (pin "A2") (pinfunction "LVDS_0A_A2") (pintype "passive"))
    )
    (net (code "77") (name "B15_L16_N") (class "Default")
      (node (ref "JM2") (pin "23") (pinfunction "23_23") (pintype "bidirectional"))
    )
    (net (code "78") (name "B15_L16_P") (class "Default")
      (node (ref "JM2") (pin "25") (pinfunction "25_25") (pintype "bidirectional"))
    )
    (net (code "79") (name "B15_L17_N") (class "Default")
      (node (ref "JM2") (pin "31") (pinfunction "31_31") (pintype "bidirectional"))
    )
    (net (code "80") (name "B15_L17_P") (class "Default")
      (node (ref "JM2") (pin "33") (pinfunction "33_33") (pintype "bidirectional"))
    )
    (net (code "81") (name "B15_L18_N") (class "Default")
      (node (ref "JM2") (pin "27") (pinfunction "27_27") (pintype "bidirectional"))
      (node (ref "PCIE-SOUTH") (pin "A17") (pinfunction "LVDS_4B_A17") (pintype "passive"))
    )
    (net (code "82") (name "B15_L18_P") (class "Default")
      (node (ref "JM2") (pin "29") (pinfunction "29_29") (pintype "bidirectional"))
      (node (ref "PCIE-SOUTH") (pin "A16") (pinfunction "LVDS_4A_A16") (pintype "passive"))
    )
    (net (code "83") (name "B15_L19_N") (class "Default")
      (node (ref "JM2") (pin "41") (pinfunction "41_41") (pintype "bidirectional"))
      (node (ref "PCIE-SOUTH") (pin "B17") (pinfunction "LVDS_5B_B17") (pintype "passive"))
    )
    (net (code "84") (name "B15_L19_P") (class "Default")
      (node (ref "JM2") (pin "43") (pinfunction "43_43") (pintype "bidirectional"))
      (node (ref "PCIE-SOUTH") (pin "B16") (pinfunction "LVDS_5A_B16") (pintype "passive"))
    )
    (net (code "85") (name "B15_L20_N") (class "Default")
      (node (ref "JM2") (pin "50") (pinfunction "50_50") (pintype "bidirectional"))
    )
    (net (code "86") (name "B15_L20_P") (class "Default")
      (node (ref "JM2") (pin "52") (pinfunction "52_52") (pintype "bidirectional"))
    )
    (net (code "87") (name "B15_L21_N") (class "Default")
      (node (ref "JM2") (pin "45") (pinfunction "45_45") (pintype "bidirectional"))
    )
    (net (code "88") (name "B15_L21_P") (class "Default")
      (node (ref "JM2") (pin "47") (pinfunction "47_47") (pintype "bidirectional"))
    )
    (net (code "89") (name "B15_L22_N") (class "Default")
      (node (ref "JM2") (pin "46") (pinfunction "46_46") (pintype "bidirectional"))
      (node (ref "PCIE-SOUTH") (pin "A3") (pinfunction "LVDS_0B_A3") (pintype "passive"))
    )
    (net (code "90") (name "B15_L22_P") (class "Default")
      (node (ref "JM2") (pin "48") (pinfunction "48_48") (pintype "bidirectional"))
      (node (ref "PCIE-SOUTH") (pin "A2") (pinfunction "LVDS_0A_A2") (pintype "passive"))
    )
    (net (code "91") (name "B15_L23_N") (class "Default")
      (node (ref "JM2") (pin "51") (pinfunction "51_51") (pintype "bidirectional"))
      (node (ref "PCIE-SOUTH") (pin "A13") (pinfunction "LVDS_3A_A13") (pintype "passive"))
    )
    (net (code "92") (name "B15_L23_P") (class "Default")
      (node (ref "JM2") (pin "49") (pinfunction "49_49") (pintype "bidirectional"))
      (node (ref "PCIE-SOUTH") (pin "A14") (pinfunction "LVDS_3B_A14") (pintype "passive"))
    )
    (net (code "93") (name "B15_L24_N") (class "Default")
      (node (ref "JM2") (pin "37") (pinfunction "37_37") (pintype "bidirectional"))
    )
    (net (code "94") (name "B15_L24_P") (class "Default")
      (node (ref "JM2") (pin "39") (pinfunction "39_39") (pintype "bidirectional"))
    )
    (net (code "95") (name "B34_L1_N") (class "Default")
      (node (ref "JM1") (pin "37") (pinfunction "37_37") (pintype "bidirectional"))
    )
    (net (code "96") (name "B34_L1_P") (class "Default")
      (node (ref "JM1") (pin "35") (pinfunction "35_35") (pintype "bidirectional"))
    )
    (net (code "97") (name "B34_L2_N") (class "Default")
      (node (ref "JM1") (pin "33") (pinfunction "33_33") (pintype "bidirectional"))
    )
    (net (code "98") (name "B34_L2_P") (class "Default")
      (node (ref "JM1") (pin "31") (pinfunction "31_31") (pintype "bidirectional"))
    )
    (net (code "99") (name "B34_L3_N") (class "Default")
      (node (ref "JM1") (pin "42") (pinfunction "42_42") (pintype "bidirectional"))
      (node (ref "U4") (pin "13") (pinfunction "SCLK_13") (pintype "input"))
    )
    (net (code "100") (name "B34_L3_P") (class "Default")
      (node (ref "JM1") (pin "40") (pinfunction "40_40") (pintype "bidirectional"))
      (node (ref "U4") (pin "17") (pinfunction "GPIO0_17") (pintype "bidirectional"))
    )
    (net (code "101") (name "B34_L4_N") (class "Default")
      (node (ref "JM1") (pin "41") (pinfunction "41_41") (pintype "bidirectional"))
      (node (ref "U4") (pin "12") (pinfunction "SDOUT_12") (pintype "output"))
    )
    (net (code "102") (name "B34_L4_P") (class "Default")
      (node (ref "JM1") (pin "39") (pinfunction "39_39") (pintype "bidirectional"))
    )
    (net (code "103") (name "B34_L5_N") (class "Default")
      (node (ref "JM1") (pin "45") (pinfunction "45_45") (pintype "bidirectional"))
      (node (ref "U4") (pin "10") (pinfunction "~{CS}_10") (pintype "input"))
    )
    (net (code "104") (name "B34_L5_P") (class "Default")
      (node (ref "JM1") (pin "43") (pinfunction "43_43") (pintype "bidirectional"))
      (node (ref "U4") (pin "11") (pinfunction "SDIN_11") (pintype "input"))
    )
    (net (code "105") (name "B34_L6_N") (class "Default")
      (node (ref "JM1") (pin "34") (pinfunction "34_34") (pintype "bidirectional"))
    )
    (net (code "106") (name "B34_L6_P") (class "Default")
      (node (ref "JM1") (pin "32") (pinfunction "32_32") (pintype "bidirectional"))
    )
    (net (code "107") (name "B34_L7_N") (class "Default")
      (node (ref "JM1") (pin "38") (pinfunction "38_38") (pintype "bidirectional"))
      (node (ref "U4") (pin "18") (pinfunction "GPIO1_18") (pintype "bidirectional"))
    )
    (net (code "108") (name "B34_L7_P") (class "Default")
      (node (ref "JM1") (pin "36") (pinfunction "36_36") (pintype "bidirectional"))
    )
    (net (code "109") (name "B34_L8_N") (class "Default")
      (node (ref "JM1") (pin "52") (pinfunction "52_52") (pintype "bidirectional"))
      (node (ref "U3") (pin "13") (pinfunction "SCLK_13") (pintype "input"))
    )
    (net (code "110") (name "B34_L8_P") (class "Default")
      (node (ref "JM1") (pin "50") (pinfunction "50_50") (pintype "bidirectional"))
      (node (ref "U3") (pin "12") (pinfunction "SDOUT_12") (pintype "output"))
    )
    (net (code "111") (name "B34_L9_N") (class "Default")
      (node (ref "JM1") (pin "46") (pinfunction "46_46") (pintype "bidirectional"))
      (node (ref "U4") (pin "33") (pinfunction "GPIO2_33") (pintype "bidirectional"))
    )
    (net (code "112") (name "B34_L9_P") (class "Default")
      (node (ref "JM1") (pin "44") (pinfunction "44_44") (pintype "bidirectional"))
      (node (ref "U4") (pin "36") (pinfunction "GPIO3_36") (pintype "bidirectional"))
    )
    (net (code "113") (name "B34_L10_N") (class "Default")
      (node (ref "JM1") (pin "51") (pinfunction "51_51") (pintype "bidirectional"))
      (node (ref "U5") (pin "11") (pinfunction "SDIN_11") (pintype "input"))
    )
    (net (code "114") (name "B34_L10_P") (class "Default")
      (node (ref "JM1") (pin "49") (pinfunction "49_49") (pintype "bidirectional"))
      (node (ref "U5") (pin "10") (pinfunction "~{CS}_10") (pintype "input"))
    )
    (net (code "115") (name "B34_L11_N") (class "Default")
      (node (ref "JM1") (pin "53") (pinfunction "53_53") (pintype "bidirectional"))
      (node (ref "U5") (pin "12") (pinfunction "SDOUT_12") (pintype "output"))
    )
    (net (code "116") (name "B34_L11_P") (class "Default")
      (node (ref "JM1") (pin "55") (pinfunction "55_55") (pintype "bidirectional"))
      (node (ref "U5") (pin "17") (pinfunction "GPIO0_17") (pintype "bidirectional"))
    )
    (net (code "117") (name "B34_L12_N") (class "Default")
      (node (ref "JM1") (pin "57") (pinfunction "57_57") (pintype "bidirectional"))
      (node (ref "U5") (pin "18") (pinfunction "GPIO1_18") (pintype "bidirectional"))
    )
    (net (code "118") (name "B34_L12_P") (class "Default")
      (node (ref "JM1") (pin "59") (pinfunction "59_59") (pintype "bidirectional"))
      (node (ref "U3") (pin "11") (pinfunction "SDIN_11") (pintype "input"))
    )
    (net (code "119") (name "B34_L13_N") (class "Default")
      (node (ref "JM1") (pin "56") (pinfunction "56_56") (pintype "bidirectional"))
      (node (ref "U3") (pin "18") (pinfunction "GPIO1_18") (pintype "bidirectional"))
    )
    (net (code "120") (name "B34_L13_P") (class "Default")
      (node (ref "JM1") (pin "54") (pinfunction "54_54") (pintype "bidirectional"))
      (node (ref "U3") (pin "17") (pinfunction "GPIO0_17") (pintype "bidirectional"))
    )
    (net (code "121") (name "B34_L14_N") (class "Default")
      (node (ref "JM1") (pin "60") (pinfunction "60_60") (pintype "bidirectional"))
      (node (ref "U3") (pin "36") (pinfunction "GPIO3_36") (pintype "bidirectional"))
    )
    (net (code "122") (name "B34_L14_P") (class "Default")
      (node (ref "JM1") (pin "58") (pinfunction "58_58") (pintype "bidirectional"))
      (node (ref "U3") (pin "33") (pinfunction "GPIO2_33") (pintype "bidirectional"))
    )
    (net (code "123") (name "B34_L15_N") (class "Default")
      (node (ref "JM1") (pin "62") (pinfunction "62_62") (pintype "bidirectional"))
    )
    (net (code "124") (name "B34_L15_P") (class "Default")
      (node (ref "JM1") (pin "64") (pinfunction "64_64") (pintype "bidirectional"))
    )
    (net (code "125") (name "B34_L16_N") (class "Default")
      (node (ref "JM1") (pin "68") (pinfunction "68_68") (pintype "bidirectional"))
    )
    (net (code "126") (name "B34_L16_P") (class "Default")
      (node (ref "JM1") (pin "70") (pinfunction "70_70") (pintype "bidirectional"))
      (node (ref "U4") (pin "32") (pinfunction "RCLK_32") (pintype "input"))
    )
    (net (code "127") (name "B34_L17_N") (class "Default")
      (node (ref "JM1") (pin "63") (pinfunction "63_63") (pintype "bidirectional"))
      (node (ref "U3") (pin "10") (pinfunction "~{CS}_10") (pintype "input"))
    )
    (net (code "128") (name "B34_L17_P") (class "Default")
      (node (ref "JM1") (pin "65") (pinfunction "65_65") (pintype "bidirectional"))
      (node (ref "U5") (pin "36") (pinfunction "GPIO3_36") (pintype "bidirectional"))
    )
    (net (code "129") (name "B34_L18_N") (class "Default")
      (node (ref "JM1") (pin "74") (pinfunction "74_74") (pintype "bidirectional"))
    )
    (net (code "130") (name "B34_L18_P") (class "Default")
      (node (ref "JM1") (pin "72") (pinfunction "72_72") (pintype "bidirectional"))
    )
    (net (code "131") (name "B34_L19_N") (class "Default")
      (node (ref "JM1") (pin "71") (pinfunction "71_71") (pintype "bidirectional"))
    )
    (net (code "132") (name "B34_L19_P") (class "Default")
      (node (ref "JM1") (pin "73") (pinfunction "73_73") (pintype "bidirectional"))
      (node (ref "U5") (pin "32") (pinfunction "RCLK_32") (pintype "input"))
    )
    (net (code "133") (name "B34_L20_N") (class "Default")
      (node (ref "JM1") (pin "76") (pinfunction "76_76") (pintype "bidirectional"))
      (node (ref "R6") (pin "1") (pinfunction "1_1") (pintype "passive"))
    )
    (net (code "134") (name "B34_L20_P") (class "Default")
      (node (ref "JM1") (pin "78") (pinfunction "78_78") (pintype "bidirectional"))
      (node (ref "R7") (pin "1") (pinfunction "1_1") (pintype "passive"))
    )
    (net (code "135") (name "B34_L21_N") (class "Default")
      (node (ref "JM1") (pin "69") (pinfunction "69_69") (pintype "bidirectional"))
    )
    (net (code "136") (name "B34_L21_P") (class "Default")
      (node (ref "JM1") (pin "67") (pinfunction "67_67") (pintype "bidirectional"))
      (node (ref "U5") (pin "33") (pinfunction "GPIO2_33") (pintype "bidirectional"))
    )
    (net (code "137") (name "B34_L22_N") (class "Default")
      (node (ref "JM1") (pin "75") (pinfunction "75_75") (pintype "bidirectional"))
    )
    (net (code "138") (name "B34_L22_P") (class "Default")
      (node (ref "JM1") (pin "77") (pinfunction "77_77") (pintype "bidirectional"))
    )
    (net (code "139") (name "B34_L23_N") (class "Default")
      (node (ref "JM1") (pin "79") (pinfunction "79_79") (pintype "bidirectional"))
    )
    (net (code "140") (name "B34_L23_P") (class "Default")
      (node (ref "JM1") (pin "81") (pinfunction "81_81") (pintype "bidirectional"))
    )
    (net (code "141") (name "B34_L24_N") (class "Default")
      (node (ref "JM1") (pin "80") (pinfunction "80_80") (pintype "bidirectional"))
      (node (ref "R8") (pin "1") (pinfunction "1_1") (pintype "passive"))
    )
    (net (code "142") (name "B34_L24_P") (class "Default")
      (node (ref "JM1") (pin "82") (pinfunction "82_82") (pintype "bidirectional"))
      (node (ref "R9") (pin "1") (pinfunction "1_1") (pintype "passive"))
    )
    (net (code "143") (name "BOOTMODE") (class "Default")
      (node (ref "JM2") (pin "100") (pinfunction "100_100") (pintype "bidirectional"))
    )
    (net (code "144") (name "DONE") (class "Default")
      (node (ref "D5") (pin "A") (pinfunction "A_A") (pintype "passive"))
      (node (ref "JM1") (pin "96") (pinfunction "96_96") (pintype "bidirectional"))
      (node (ref "R4") (pin "1") (pinfunction "1_1") (pintype "passive"))
    )
    (net (code "145") (name "EN_A") (class "Default")
      (node (ref "R99") (pin "1") (pinfunction "1_1") (pintype "passive"))
      (node (ref "U6") (pin "1") (pinfunction "EN_1") (pintype "input"))
    )
    (net (code "146") (name "EN_B") (class "Default")
      (node (ref "R21") (pin "1") (pinfunction "1_1") (pintype "passive"))
      (node (ref "U7") (pin "1") (pinfunction "EN_1") (pintype "input"))
    )
    (net (code "147") (name "GND") (class "Default")
      (node (ref "C1") (pin "2") (pinfunction "2_2") (pintype "passive"))
      (node (ref "C10") (pin "2") (pinfunction "2_2") (pintype "passive"))
      (node (ref "C11") (pin "2") (pinfunction "2_2") (pintype "passive"))
      (node (ref "C12") (pin "2") (pinfunction "2_2") (pintype "passive"))
      (node (ref "C13") (pin "2") (pinfunction "2_2") (pintype "passive"))
      (node (ref "C14") (pin "2") (pinfunction "2_2") (pintype "passive"))
      (node (ref "C15") (pin "2") (pinfunction "2_2") (pintype "passive"))
      (node (ref "C16") (pin "2") (pinfunction "2_2") (pintype "passive"))
      (node (ref "C17") (pin "2") (pinfunction "2_2") (pintype "passive"))
      (node (ref "C18") (pin "2") (pinfunction "2_2") (pintype "passive"))
      (node (ref "C19") (pin "2") (pinfunction "2_2") (pintype "passive"))
      (node (ref "C25") (pin "2") (pinfunction "2_2") (pintype "passive"))
      (node (ref "C26") (pin "2") (pinfunction "2_2") (pintype "passive"))
      (node (ref "C27") (pin "2") (pinfunction "2_2") (pintype "passive"))
      (node (ref "C28") (pin "2") (pinfunction "2_2") (pintype "passive"))
      (node (ref "C29") (pin "2") (pinfunction "2_2") (pintype "passive"))
      (node (ref "C30") (pin "2") (pinfunction "2_2") (pintype "passive"))
      (node (ref "C31") (pin "2") (pinfunction "2_2") (pintype "passive"))
      (node (ref "C32") (pin "2") (pinfunction "2_2") (pintype "passive"))
      (node (ref "C33") (pin "2") (pinfunction "2_2") (pintype "passive"))
      (node (ref "C34") (pin "2") (pinfunction "2_2") (pintype "passive"))
      (node (ref "C35") (pin "2") (pinfunction "2_2") (pintype "passive"))
      (node (ref "C36") (pin "2") (pinfunction "2_2") (pintype "passive"))
      (node (ref "C37") (pin "2") (pinfunction "2_2") (pintype "passive"))
      (node (ref "C4") (pin "2") (pinfunction "2_2") (pintype "passive"))
      (node (ref "C43") (pin "2") (pinfunction "2_2") (pintype "passive"))
      (node (ref "C44") (pin "2") (pinfunction "2_2") (pintype "passive"))
      (node (ref "C45") (pin "2") (pinfunction "2_2") (pintype "passive"))
      (node (ref "C46") (pin "2") (pinfunction "2_2") (pintype "passive"))
      (node (ref "C47") (pin "2") (pinfunction "2_2") (pintype "passive"))
      (node (ref "C48") (pin "2") (pinfunction "2_2") (pintype "passive"))
      (node (ref "C49") (pin "2") (pinfunction "2_2") (pintype "passive"))
      (node (ref "C50") (pin "2") (pinfunction "2_2") (pintype "passive"))
      (node (ref "C51") (pin "2") (pinfunction "2_2") (pintype "passive"))
      (node (ref "C52") (pin "2") (pinfunction "2_2") (pintype "passive"))
      (node (ref "C53") (pin "2") (pinfunction "2_2") (pintype "passive"))
      (node (ref "C54") (pin "2") (pinfunction "2_2") (pintype "passive"))
      (node (ref "C55") (pin "2") (pinfunction "2_2") (pintype "passive"))
      (node (ref "C56") (pin "2") (pinfunction "2_2") (pintype "passive"))
      (node (ref "C57") (pin "2") (pinfunction "2_2") (pintype "passive"))
      (node (ref "C58") (pin "2") (pinfunction "2_2") (pintype "passive"))
      (node (ref "C59") (pin "2") (pinfunction "2_2") (pintype "passive"))
      (node (ref "C8") (pin "2") (pinfunction "2_2") (pintype "passive"))
      (node (ref "C9") (pin "2") (pinfunction "2_2") (pintype "passive"))
      (node (ref "D5") (pin "C") (pinfunction "C_C") (pintype "passive"))
      (node (ref "JM1") (pin "100") (pinfunction "100_100") (pintype "bidirectional"))
      (node (ref "JM1") (pin "11") (pinfunction "11_11") (pintype "bidirectional"))
      (node (ref "JM1") (pin "12") (pinfunction "12_12") (pintype "bidirectional"))
      (node (ref "JM1") (pin "17") (pinfunction "17_17") (pintype "bidirectional"))
      (node (ref "JM1") (pin "18") (pinfunction "18_18") (pintype "bidirectional"))
      (node (ref "JM1") (pin "23") (pinfunction "23_23") (pintype "bidirectional"))
      (node (ref "JM1") (pin "24") (pinfunction "24_24") (pintype "bidirectional"))
      (node (ref "JM1") (pin "29") (pinfunction "29_29") (pintype "bidirectional"))
      (node (ref "JM1") (pin "30") (pinfunction "30_30") (pintype "bidirectional"))
      (node (ref "JM1") (pin "47") (pinfunction "47_47") (pintype "bidirectional"))
      (node (ref "JM1") (pin "48") (pinfunction "48_48") (pintype "bidirectional"))
      (node (ref "JM1") (pin "5") (pinfunction "5_5") (pintype "bidirectional"))
      (node (ref "JM1") (pin "6") (pinfunction "6_6") (pintype "bidirectional"))
      (node (ref "JM1") (pin "66") (pinfunction "66_66") (pintype "bidirectional"))
      (node (ref "JM1") (pin "84") (pinfunction "84_84") (pintype "bidirectional"))
      (node (ref "JM1") (pin "98") (pinfunction "98_98") (pintype "bidirectional"))
      (node (ref "JM1") (pin "F1") (pinfunction "F1_F1") (pintype "bidirectional"))
      (node (ref "JM1") (pin "F2") (pinfunction "F2_F2") (pintype "bidirectional"))
      (node (ref "JM2") (pin "17") (pinfunction "17_17") (pintype "bidirectional"))
      (node (ref "JM2") (pin "35") (pinfunction "35_35") (pintype "bidirectional"))
      (node (ref "JM2") (pin "36") (pinfunction "36_36") (pintype "bidirectional"))
      (node (ref "JM2") (pin "72") (pinfunction "72_72") (pintype "bidirectional"))
      (node (ref "JM2") (pin "83") (pinfunction "83_83") (pintype "bidirectional"))
      (node (ref "JM2") (pin "90") (pinfunction "90_90") (pintype "bidirectional"))
      (node (ref "JM2") (pin "F1") (pinfunction "F1_F1") (pintype "bidirectional"))
      (node (ref "JM2") (pin "F2") (pinfunction "F2_F2") (pintype "bidirectional"))
      (node (ref "JP2") (pin "3") (pinfunction "3_3") (pintype "passive"))
      (node (ref "JTAG") (pin "1") (pinfunction "1_1") (pintype "passive"))
      (node (ref "JTAG") (pin "11") (pinfunction "11_11") (pintype "passive"))
      (node (ref "JTAG") (pin "13") (pinfunction "13_13") (pintype "passive"))
      (node (ref "JTAG") (pin "3") (pinfunction "3_3") (pintype "passive"))
      (node (ref "JTAG") (pin "5") (pinfunction "5_5") (pintype "passive"))
      (node (ref "JTAG") (pin "7") (pinfunction "7_7") (pintype "passive"))
      (node (ref "JTAG") (pin "9") (pinfunction "9_9") (pintype "passive"))
      (node (ref "OUT1") (pin "2@1") (pinfunction "GND_2@1") (pintype "passive"))
      (node (ref "OUT1") (pin "2@2") (pinfunction "GND_2@2") (pintype "passive"))
      (node (ref "OUT1") (pin "2@3") (pinfunction "GND_2@3") (pintype "passive"))
      (node (ref "OUT2") (pin "2@1") (pinfunction "GND_2@1") (pintype "passive"))
      (node (ref "OUT2") (pin "2@2") (pinfunction "GND_2@2") (pintype "passive"))
      (node (ref "OUT2") (pin "2@3") (pinfunction "GND_2@3") (pintype "passive"))
      (node (ref "PCIE-NORTH") (pin "A1") (pinfunction "GND_A1") (pintype "passive"))
      (node (ref "PCIE-NORTH") (pin "A10") (pinfunction "GND_A10") (pintype "passive"))
      (node (ref "PCIE-NORTH") (pin "A12") (pinfunction "GND_A12") (pintype "passive"))
      (node (ref "PCIE-NORTH") (pin "A15") (pinfunction "GND_A15") (pintype "passive"))
      (node (ref "PCIE-NORTH") (pin "A18") (pinfunction "GND_A18") (pintype "passive"))
      (node (ref "PCIE-NORTH") (pin "A4") (pinfunction "GND_A4") (pintype "passive"))
      (node (ref "PCIE-NORTH") (pin "A7") (pinfunction "GND_A7") (pintype "passive"))
      (node (ref "PCIE-NORTH") (pin "B15") (pinfunction "GND_B15") (pintype "passive"))
      (node (ref "PCIE-NORTH") (pin "B18") (pinfunction "GND_B18") (pintype "passive"))
      (node (ref "PCIE-SOUTH") (pin "A1") (pinfunction "GND_A1") (pintype "passive"))
      (node (ref "PCIE-SOUTH") (pin "A10") (pinfunction "GND_A10") (pintype "passive"))
      (node (ref "PCIE-SOUTH") (pin "A12") (pinfunction "GND_A12") (pintype "passive"))
      (node (ref "PCIE-SOUTH") (pin "A15") (pinfunction "GND_A15") (pintype "passive"))
      (node (ref "PCIE-SOUTH") (pin "A18") (pinfunction "GND_A18") (pintype "passive"))
      (node (ref "PCIE-SOUTH") (pin "A4") (pinfunction "GND_A4") (pintype "passive"))
      (node (ref "PCIE-SOUTH") (pin "A7") (pinfunction "GND_A7") (pintype "passive"))
      (node (ref "PCIE-SOUTH") (pin "B15") (pinfunction "GND_B15") (pintype "passive"))
      (node (ref "PCIE-SOUTH") (pin "B18") (pinfunction "GND_B18") (pintype "passive"))
      (node (ref "R10") (pin "2") (pinfunction "2_2") (pintype "passive"))
      (node (ref "R11") (pin "2") (pinfunction "2_2") (pintype "passive"))
      (node (ref "R12") (pin "2") (pinfunction "2_2") (pintype "passive"))
      (node (ref "R13") (pin "2") (pinfunction "2_2") (pintype "passive"))
      (node (ref "R14") (pin "2") (pinfunction "2_2") (pintype "passive"))
      (node (ref "R15") (pin "2") (pinfunction "2_2") (pintype "passive"))
      (node (ref "R16") (pin "2") (pinfunction "2_2") (pintype "passive"))
      (node (ref "R18") (pin "1") (pinfunction "1_1") (pintype "passive"))
      (node (ref "R20") (pin "1") (pinfunction "1_1") (pintype "passive"))
      (node (ref "R3") (pin "2") (pinfunction "2_2") (pintype "passive"))
      (node (ref "SDI-IN") (pin "2@1") (pinfunction "GND_2@1") (pintype "passive"))
      (node (ref "SDI-IN") (pin "2@2") (pinfunction "GND_2@2") (pintype "passive"))
      (node (ref "SDI-IN") (pin "2@3") (pinfunction "GND_2@3") (pintype "passive"))
      (node (ref "U1") (pin "3") (pinfunction "GND_3") (pintype "passive"))
      (node (ref "U2") (pin "1") (pinfunction "A0_1") (pintype "input"))
      (node (ref "U2") (pin "2") (pinfunction "A1_2") (pintype "input"))
      (node (ref "U2") (pin "3") (pinfunction "A2_3") (pintype "input"))
      (node (ref "U2") (pin "4") (pinfunction "GND_4") (pintype "passive"))
      (node (ref "U2") (pin "EP") (pinfunction "EP_EP") (pintype "passive"))
      (node (ref "U3") (pin "1") (pinfunction "VEE_SDI_1") (pintype "power_in"))
      (node (ref "U3") (pin "14") (pinfunction "VSS_14") (pintype "power_in"))
      (node (ref "U3") (pin "15") (pinfunction "VSS_15") (pintype "power_in"))
      (node (ref "U3") (pin "19") (pinfunction "VEE_CORE_19") (pintype "power_in"))
      (node (ref "U3") (pin "21") (pinfunction "VEEO_21") (pintype "power_in"))
      (node (ref "U3") (pin "28") (pinfunction "VEEO_28") (pintype "power_in"))
      (node (ref "U3") (pin "31") (pinfunction "VEE_CORE_31") (pintype "power_in"))
      (node (ref "U3") (pin "37") (pinfunction "VEE_CORE_37") (pintype "power_in"))
      (node (ref "U3") (pin "38") (pinfunction "VEE_CORE_38") (pintype "power_in"))
      (node (ref "U3") (pin "8") (pinfunction "VEE_SDI_8") (pintype "power_in"))
      (node (ref "U4") (pin "1") (pinfunction "VEE_DDI_1") (pintype "power_in"))
      (node (ref "U4") (pin "14") (pinfunction "VSS_14") (pintype "power_in"))
      (node (ref "U4") (pin "15") (pinfunction "VSS_15") (pintype "power_in"))
      (node (ref "U4") (pin "19") (pinfunction "VEE_CORE_19") (pintype "power_in"))
      (node (ref "U4") (pin "21") (pinfunction "VEEO_21") (pintype "power_in"))
      (node (ref "U4") (pin "28") (pinfunction "VEEO_28") (pintype "power_in"))
      (node (ref "U4") (pin "31") (pinfunction "VEE_CORE_31") (pintype "power_in"))
      (node (ref "U4") (pin "37") (pinfunction "VEE_CORE_37") (pintype "power_in"))
      (node (ref "U4") (pin "38") (pinfunction "VEE_CORE_38") (pintype "power_in"))
      (node (ref "U4") (pin "8") (pinfunction "VEE_DDI_8") (pintype "power_in"))
      (node (ref "U5") (pin "1") (pinfunction "VEE_DDI_1") (pintype "power_in"))
      (node (ref "U5") (pin "14") (pinfunction "VSS_14") (pintype "power_in"))
      (node (ref "U5") (pin "15") (pinfunction "VSS_15") (pintype "power_in"))
      (node (ref "U5") (pin "19") (pinfunction "VEE_CORE_19") (pintype "power_in"))
      (node (ref "U5") (pin "21") (pinfunction "VEEO_21") (pintype "power_in"))
      (node (ref "U5") (pin "28") (pinfunction "VEEO_28") (pintype "power_in"))
      (node (ref "U5") (pin "31") (pinfunction "VEE_CORE_31") (pintype "power_in"))
      (node (ref "U5") (pin "37") (pinfunction "VEE_CORE_37") (pintype "power_in"))
      (node (ref "U5") (pin "38") (pinfunction "VEE_CORE_38") (pintype "power_in"))
      (node (ref "U5") (pin "8") (pinfunction "VEE_DDI_8") (pintype "power_in"))
      (node (ref "U6") (pin "5") (pinfunction "GND_5") (pintype "passive"))
      (node (ref "U6") (pin "6") (pinfunction "GND_6") (pintype "passive"))
      (node (ref "U6") (pin "EP") (pinfunction "GND_EP") (pintype "passive"))
      (node (ref "U7") (pin "5") (pinfunction "GND_5") (pintype "passive"))
      (node (ref "U7") (pin "6") (pinfunction "GND_6") (pintype "passive"))
      (node (ref "U7") (pin "EP") (pinfunction "GND_EP") (pintype "passive"))
    )
    (net (code "148") (name "I2C_V") (class "Default")
      (node (ref "C4") (pin "1") (pinfunction "1_1") (pintype "passive"))
      (node (ref "PCIE-NORTH") (pin "B3") (pinfunction "V_I2C_B3") (pintype "passive"))
      (node (ref "R2") (pin "1") (pinfunction "1_1") (pintype "passive"))
      (node (ref "U2") (pin "8") (pinfunction "VCC_8") (pintype "power_in"))
    )
    (net (code "149") (name "MGT_CLK0_N") (class "Default")
      (node (ref "C3") (pin "2") (pinfunction "2_2") (pintype "passive"))
      (node (ref "JM1") (pin "4") (pinfunction "4_4") (pintype "bidirectional"))
    )
    (net (code "150") (name "MGT_CLK0_P") (class "Default")
      (node (ref "C2") (pin "2") (pinfunction "2_2") (pintype "passive"))
      (node (ref "JM1") (pin "2") (pinfunction "2_2") (pintype "bidirectional"))
    )
    (net (code "151") (name "MGT_RX0_N") (class "Default")
      (node (ref "JM1") (pin "21") (pinfunction "21_21") (pintype "bidirectional"))
      (node (ref "U3") (pin "27") (pinfunction "DDO0_27") (pintype "output"))
    )
    (net (code "152") (name "MGT_RX0_P") (class "Default")
      (node (ref "JM1") (pin "19") (pinfunction "19_19") (pintype "bidirectional"))
      (node (ref "U3") (pin "26") (pinfunction "~{DDO0}_26") (pintype "output"))
    )
    (net (code "153") (name "MGT_RX1_N") (class "Default")
      (node (ref "JM1") (pin "15") (pinfunction "15_15") (pintype "bidirectional"))
      (node (ref "U3") (pin "23") (pinfunction "DDO1/RCO_23") (pintype "output"))
    )
    (net (code "154") (name "MGT_RX1_P") (class "Default")
      (node (ref "JM1") (pin "13") (pinfunction "13_13") (pintype "bidirectional"))
      (node (ref "U3") (pin "22") (pinfunction "~{DDO1}/~{RCO}_22") (pintype "output"))
    )
    (net (code "155") (name "MGT_RX2_N") (class "Default")
      (node (ref "JM1") (pin "9") (pinfunction "9_9") (pintype "bidirectional"))
    )
    (net (code "156") (name "MGT_RX2_P") (class "Default")
      (node (ref "JM1") (pin "7") (pinfunction "7_7") (pintype "bidirectional"))
    )
    (net (code "157") (name "MGT_RX3_N") (class "Default")
      (node (ref "JM1") (pin "3") (pinfunction "3_3") (pintype "bidirectional"))
    )
    (net (code "158") (name "MGT_RX3_P") (class "Default")
      (node (ref "JM1") (pin "1") (pinfunction "1_1") (pintype "bidirectional"))
    )
    (net (code "159") (name "MGT_TX0_N") (class "Default")
      (node (ref "JM1") (pin "28") (pinfunction "28_28") (pintype "bidirectional"))
      (node (ref "U5") (pin "6") (pinfunction "DDI_6") (pintype "input"))
    )
    (net (code "160") (name "MGT_TX0_P") (class "Default")
      (node (ref "JM1") (pin "26") (pinfunction "26_26") (pintype "bidirectional"))
      (node (ref "U5") (pin "7") (pinfunction "~{DDI}_7") (pintype "input"))
    )
    (net (code "161") (name "MGT_TX1_N") (class "Default")
      (node (ref "JM1") (pin "22") (pinfunction "22_22") (pintype "bidirectional"))
      (node (ref "U4") (pin "6") (pinfunction "DDI_6") (pintype "input"))
    )
    (net (code "162") (name "MGT_TX1_P") (class "Default")
      (node (ref "JM1") (pin "20") (pinfunction "20_20") (pintype "bidirectional"))
      (node (ref "U4") (pin "7") (pinfunction "~{DDI}_7") (pintype "input"))
    )
    (net (code "163") (name "MGT_TX2_N") (class "Default")
      (node (ref "JM1") (pin "16") (pinfunction "16_16") (pintype "bidirectional"))
    )
    (net (code "164") (name "MGT_TX2_P") (class "Default")
      (node (ref "JM1") (pin "14") (pinfunction "14_14") (pintype "bidirectional"))
    )
    (net (code "165") (name "MGT_TX3_N") (class "Default")
      (node (ref "JM1") (pin "10") (pinfunction "10_10") (pintype "bidirectional"))
    )
    (net (code "166") (name "MGT_TX3_P") (class "Default")
      (node (ref "JM1") (pin "8") (pinfunction "8_8") (pintype "bidirectional"))
    )
    (net (code "167") (name "M_1V8") (class "Default")
      (node (ref "JM2") (pin "18") (pinfunction "18_18") (pintype "bidirectional"))
      (node (ref "R5") (pin "2") (pinfunction "2_2") (pintype "passive"))
    )
    (net (code "168") (name "N$83") (class "Default")
      (node (ref "U5") (pin "13") (pinfunction "SCLK_13") (pintype "input"))
    )
    (net (code "169") (name "N_5V") (class "Default")
      (node (ref "PCIE-NORTH") (pin "B12") (pinfunction "5V_B12") (pintype "passive"))
    )
    (net (code "170") (name "N_IO0") (class "Default")
      (node (ref "PCIE-NORTH") (pin "B4") (pinfunction "IO0_B4") (pintype "passive"))
    )
    (net (code "171") (name "N_IO1") (class "Default")
      (node (ref "PCIE-NORTH") (pin "B5") (pinfunction "IO1_B5") (pintype "passive"))
    )
    (net (code "172") (name "N_IO2") (class "Default")
      (node (ref "PCIE-NORTH") (pin "B6") (pinfunction "IO2_B6") (pintype "passive"))
    )
    (net (code "173") (name "N_IO3") (class "Default")
      (node (ref "PCIE-NORTH") (pin "B7") (pinfunction "IO3_B7") (pintype "passive"))
    )
    (net (code "174") (name "N_IO4") (class "Default")
      (node (ref "PCIE-NORTH") (pin "B8") (pinfunction "IO4_B8") (pintype "passive"))
    )
    (net (code "175") (name "N_IO5") (class "Default")
      (node (ref "PCIE-NORTH") (pin "B9") (pinfunction "IO5_B9") (pintype "passive"))
    )
    (net (code "176") (name "N_IO6") (class "Default")
      (node (ref "PCIE-NORTH") (pin "B10") (pinfunction "IO6_B10") (pintype "passive"))
    )
    (net (code "177") (name "N_IO7") (class "Default")
      (node (ref "PCIE-NORTH") (pin "B11") (pinfunction "IO7_B11") (pintype "passive"))
    )
    (net (code "178") (name "N_PCIE_V") (class "Default")
      (node (ref "PCIE-NORTH") (pin "B13") (pinfunction "VCC_B13") (pintype "passive"))
    )
    (net (code "179") (name "N_VCCIO") (class "Default")
      (node (ref "PCIE-NORTH") (pin "B14") (pinfunction "VCCIO_B14") (pintype "passive"))
    )
    (net (code "180") (name "Net-(C5-Pad1)") (class "Default")
      (node (ref "C5") (pin "1") (pinfunction "1_1") (pintype "passive"))
      (node (ref "SDI-IN") (pin "1") (pinfunction "1_1") (pintype "passive"))
    )
    (net (code "181") (name "Net-(C7-Pad2)") (class "Default")
      (node (ref "C7") (pin "2") (pinfunction "2_2") (pintype "passive"))
      (node (ref "R10") (pin "1") (pinfunction "1_1") (pintype "passive"))
    )
    (net (code "182") (name "Net-(C20-Pad2)") (class "Default")
      (node (ref "C20") (pin "2") (pinfunction "2_2") (pintype "passive"))
      (node (ref "OUT1") (pin "1") (pinfunction "1_1") (pintype "passive"))
    )
    (net (code "183") (name "Net-(C21-Pad2)") (class "Default")
      (node (ref "C21") (pin "2") (pinfunction "2_2") (pintype "passive"))
      (node (ref "R11") (pin "1") (pinfunction "1_1") (pintype "passive"))
    )
    (net (code "184") (name "Net-(C22-Pad2)") (class "Default")
      (node (ref "C22") (pin "2") (pinfunction "2_2") (pintype "passive"))
      (node (ref "R12") (pin "1") (pinfunction "1_1") (pintype "passive"))
    )
    (net (code "185") (name "Net-(C23-Pad2)") (class "Default")
      (node (ref "C23") (pin "2") (pinfunction "2_2") (pintype "passive"))
      (node (ref "R13") (pin "1") (pinfunction "1_1") (pintype "passive"))
    )
    (net (code "186") (name "Net-(C38-Pad2)") (class "Default")
      (node (ref "C38") (pin "2") (pinfunction "2_2") (pintype "passive"))
      (node (ref "OUT2") (pin "1") (pinfunction "1_1") (pintype "passive"))
    )
    (net (code "187") (name "Net-(C39-Pad2)") (class "Default")
      (node (ref "C39") (pin "2") (pinfunction "2_2") (pintype "passive"))
      (node (ref "R14") (pin "1") (pinfunction "1_1") (pintype "passive"))
    )
    (net (code "188") (name "Net-(C40-Pad2)") (class "Default")
      (node (ref "C40") (pin "2") (pinfunction "2_2") (pintype "passive"))
      (node (ref "R15") (pin "1") (pinfunction "1_1") (pintype "passive"))
    )
    (net (code "189") (name "Net-(C41-Pad2)") (class "Default")
      (node (ref "C41") (pin "2") (pinfunction "2_2") (pintype "passive"))
      (node (ref "R16") (pin "1") (pinfunction "1_1") (pintype "passive"))
    )
    (net (code "190") (name "Net-(D1-PadC)") (class "Default")
      (node (ref "D1") (pin "C") (pinfunction "C_C") (pintype "passive"))
      (node (ref "R6") (pin "2") (pinfunction "2_2") (pintype "passive"))
    )
    (net (code "191") (name "Net-(D2-PadC)") (class "Default")
      (node (ref "D2") (pin "C") (pinfunction "C_C") (pintype "passive"))
      (node (ref "R7") (pin "2") (pinfunction "2_2") (pintype "passive"))
    )
    (net (code "192") (name "Net-(D3-PadC)") (class "Default")
      (node (ref "D3") (pin "C") (pinfunction "C_C") (pintype "passive"))
      (node (ref "R8") (pin "2") (pinfunction "2_2") (pintype "passive"))
    )
    (net (code "193") (name "Net-(D4-PadC)") (class "Default")
      (node (ref "D4") (pin "C") (pinfunction "C_C") (pintype "passive"))
      (node (ref "R9") (pin "2") (pinfunction "2_2") (pintype "passive"))
    )
    (net (code "194") (name "Net-(U1-OUT+)") (class "Default")
      (node (ref "C2") (pin "1") (pinfunction "1_1") (pintype "passive"))
      (node (ref "R1") (pin "1") (pinfunction "1_1") (pintype "passive"))
      (node (ref "U1") (pin "4") (pinfunction "OUT+_4") (pintype "output"))
    )
    (net (code "195") (name "Net-(U1-OUT-)") (class "Default")
      (node (ref "C3") (pin "1") (pinfunction "1_1") (pintype "passive"))
      (node (ref "R1") (pin "2") (pinfunction "2_2") (pintype "passive"))
      (node (ref "U1") (pin "5") (pinfunction "OUT-_5") (pintype "output"))
    )
    (net (code "196") (name "Net-(U2-WP)") (class "Default")
      (node (ref "R2") (pin "2") (pinfunction "2_2") (pintype "passive"))
      (node (ref "R3") (pin "1") (pinfunction "1_1") (pintype "passive"))
      (node (ref "U2") (pin "7") (pinfunction "WP_7") (pintype "input"))
    )
    (net (code "197") (name "Net-(U3-LF+)") (class "Default")
      (node (ref "C6") (pin "1") (pinfunction "1_1") (pintype "passive"))
      (node (ref "U3") (pin "39") (pinfunction "LF+_39") (pintype "passive"))
    )
    (net (code "198") (name "Net-(U3-LF-)") (class "Default")
      (node (ref "C6") (pin "2") (pinfunction "2_2") (pintype "passive"))
      (node (ref "U3") (pin "40") (pinfunction "LF-_40") (pintype "passive"))
    )
    (net (code "199") (name "Net-(U3-SDI)") (class "Default")
      (node (ref "C5") (pin "2") (pinfunction "2_2") (pintype "passive"))
      (node (ref "U3") (pin "2") (pinfunction "SDI_2") (pintype "input"))
    )
    (net (code "200") (name "Net-(U3-SDI_TERM)") (class "Default")
      (node (ref "C7") (pin "1") (pinfunction "1_1") (pintype "passive"))
      (node (ref "U3") (pin "3") (pinfunction "SDI_TERM_3") (pintype "passive"))
    )
    (net (code "201") (name "Net-(U3-VCO_FILT)") (class "Default")
      (node (ref "C8") (pin "1") (pinfunction "1_1") (pintype "passive"))
      (node (ref "U3") (pin "34") (pinfunction "VCO_FILT_34") (pintype "passive"))
    )
    (net (code "202") (name "Net-(U3-VCO_FILT10)") (class "Default")
      (node (ref "C9") (pin "1") (pinfunction "1_1") (pintype "passive"))
      (node (ref "U3") (pin "30") (pinfunction "VCO_FILT10_30") (pintype "passive"))
    )
    (net (code "203") (name "Net-(U4-LF+)") (class "Default")
      (node (ref "C24") (pin "1") (pinfunction "1_1") (pintype "passive"))
      (node (ref "U4") (pin "39") (pinfunction "LF+_39") (pintype "passive"))
    )
    (net (code "204") (name "Net-(U4-LF-)") (class "Default")
      (node (ref "C24") (pin "2") (pinfunction "2_2") (pintype "passive"))
      (node (ref "U4") (pin "40") (pinfunction "LF-_40") (pintype "passive"))
    )
    (net (code "205") (name "Net-(U4-SDO0)") (class "Default")
      (node (ref "C20") (pin "1") (pinfunction "1_1") (pintype "passive"))
      (node (ref "U4") (pin "27") (pinfunction "SDO0_27") (pintype "output"))
    )
    (net (code "206") (name "Net-(U4-SDO1{slash}RCO)") (class "Default")
      (node (ref "C22") (pin "1") (pinfunction "1_1") (pintype "passive"))
      (node (ref "U4") (pin "23") (pinfunction "SDO1/RCO_23") (pintype "output"))
    )
    (net (code "207") (name "Net-(U4-TERM)") (class "Default")
      (node (ref "C25") (pin "1") (pinfunction "1_1") (pintype "passive"))
      (node (ref "U4") (pin "5") (pinfunction "TERM_5") (pintype "passive"))
    )
    (net (code "208") (name "Net-(U4-VCO_FILT)") (class "Default")
      (node (ref "C26") (pin "1") (pinfunction "1_1") (pintype "passive"))
      (node (ref "U4") (pin "34") (pinfunction "VCO_FILT_34") (pintype "passive"))
    )
    (net (code "209") (name "Net-(U4-VCO_FILT10)") (class "Default")
      (node (ref "C27") (pin "1") (pinfunction "1_1") (pintype "passive"))
      (node (ref "U4") (pin "30") (pinfunction "VCO_FILT10_30") (pintype "passive"))
    )
    (net (code "210") (name "Net-(U4-~{SDO0})") (class "Default")
      (node (ref "C23") (pin "1") (pinfunction "1_1") (pintype "passive"))
      (node (ref "U4") (pin "26") (pinfunction "~{SDO0}_26") (pintype "output"))
    )
    (net (code "211") (name "Net-(U4-~{SDO1}{slash}~{RCO})") (class "Default")
      (node (ref "C21") (pin "1") (pinfunction "1_1") (pintype "passive"))
      (node (ref "U4") (pin "22") (pinfunction "~{SDO1}/~{RCO}_22") (pintype "output"))
    )
    (net (code "212") (name "Net-(U5-LF+)") (class "Default")
      (node (ref "C42") (pin "1") (pinfunction "1_1") (pintype "passive"))
      (node (ref "U5") (pin "39") (pinfunction "LF+_39") (pintype "passive"))
    )
    (net (code "213") (name "Net-(U5-LF-)") (class "Default")
      (node (ref "C42") (pin "2") (pinfunction "2_2") (pintype "passive"))
      (node (ref "U5") (pin "40") (pinfunction "LF-_40") (pintype "passive"))
    )
    (net (code "214") (name "Net-(U5-SDO0)") (class "Default")
      (node (ref "C41") (pin "1") (pinfunction "1_1") (pintype "passive"))
      (node (ref "U5") (pin "27") (pinfunction "SDO0_27") (pintype "output"))
    )
    (net (code "215") (name "Net-(U5-SDO1{slash}RCO)") (class "Default")
      (node (ref "C38") (pin "1") (pinfunction "1_1") (pintype "passive"))
      (node (ref "U5") (pin "23") (pinfunction "SDO1/RCO_23") (pintype "output"))
    )
    (net (code "216") (name "Net-(U5-TERM)") (class "Default")
      (node (ref "C43") (pin "1") (pinfunction "1_1") (pintype "passive"))
      (node (ref "U5") (pin "5") (pinfunction "TERM_5") (pintype "passive"))
    )
    (net (code "217") (name "Net-(U5-VCO_FILT)") (class "Default")
      (node (ref "C44") (pin "1") (pinfunction "1_1") (pintype "passive"))
      (node (ref "U5") (pin "34") (pinfunction "VCO_FILT_34") (pintype "passive"))
    )
    (net (code "218") (name "Net-(U5-VCO_FILT10)") (class "Default")
      (node (ref "C45") (pin "1") (pinfunction "1_1") (pintype "passive"))
      (node (ref "U5") (pin "30") (pinfunction "VCO_FILT10_30") (pintype "passive"))
    )
    (net (code "219") (name "Net-(U5-~{SDO0})") (class "Default")
      (node (ref "C40") (pin "1") (pinfunction "1_1") (pintype "passive"))
      (node (ref "U5") (pin "26") (pinfunction "~{SDO0}_26") (pintype "output"))
    )
    (net (code "220") (name "Net-(U5-~{SDO1}{slash}~{RCO})") (class "Default")
      (node (ref "C39") (pin "1") (pinfunction "1_1") (pintype "passive"))
      (node (ref "U5") (pin "22") (pinfunction "~{SDO1}/~{RCO}_22") (pintype "output"))
    )
    (net (code "221") (name "Net-(U6-FB)") (class "Default")
      (node (ref "R17") (pin "1") (pinfunction "1_1") (pintype "passive"))
      (node (ref "R18") (pin "2") (pinfunction "2_2") (pintype "passive"))
      (node (ref "U6") (pin "7") (pinfunction "FB_7") (pintype "output"))
    )
    (net (code "222") (name "Net-(U7-FB)") (class "Default")
      (node (ref "R19") (pin "1") (pinfunction "1_1") (pintype "passive"))
      (node (ref "R20") (pin "2") (pinfunction "2_2") (pintype "passive"))
      (node (ref "U7") (pin "7") (pinfunction "FB_7") (pintype "output"))
    )
    (net (code "223") (name "PROG_B") (class "Default")
      (node (ref "JM1") (pin "94") (pinfunction "94_94") (pintype "bidirectional"))
    )
    (net (code "224") (name "SCL") (class "Default")
      (node (ref "PCIE-NORTH") (pin "B2") (pinfunction "SCL_B2") (pintype "passive"))
      (node (ref "U2") (pin "6") (pinfunction "SCL_6") (pintype "input"))
    )
    (net (code "225") (name "SDA") (class "Default")
      (node (ref "PCIE-NORTH") (pin "B1") (pinfunction "SDA_B1") (pintype "passive"))
      (node (ref "U2") (pin "5") (pinfunction "SDA_5") (pintype "bidirectional"))
    )
    (net (code "226") (name "SPI-CLK") (class "Default")
      (node (ref "JM2") (pin "67") (pinfunction "67_67") (pintype "bidirectional"))
    )
    (net (code "227") (name "SPI-CS") (class "Default")
      (node (ref "JM2") (pin "69") (pinfunction "69_69") (pintype "bidirectional"))
    )
    (net (code "228") (name "SPI-DQ0") (class "Default")
      (node (ref "JM2") (pin "68") (pinfunction "68_68") (pintype "bidirectional"))
    )
    (net (code "229") (name "SPI-DQ1") (class "Default")
      (node (ref "JM2") (pin "71") (pinfunction "71_71") (pintype "bidirectional"))
    )
    (net (code "230") (name "SPI-DQ2") (class "Default")
      (node (ref "JM2") (pin "73") (pinfunction "73_73") (pintype "bidirectional"))
    )
    (net (code "231") (name "SPI-DQ3") (class "Default")
      (node (ref "JM2") (pin "70") (pinfunction "70_70") (pintype "bidirectional"))
    )
    (net (code "232") (name "S_5V") (class "Default")
      (node (ref "JP2") (pin "1") (pinfunction "1_1") (pintype "passive"))
      (node (ref "PCIE-SOUTH") (pin "B12") (pinfunction "5V_B12") (pintype "passive"))
    )
    (net (code "233") (name "S_PCIE_V") (class "Default")
      (node (ref "PCIE-SOUTH") (pin "B13") (pinfunction "VCC_B13") (pintype "passive"))
    )
    (net (code "234") (name "S_VCCIO") (class "Default")
      (node (ref "JM2") (pin "54") (pinfunction "54_54") (pintype "bidirectional"))
      (node (ref "PCIE-SOUTH") (pin "B14") (pinfunction "VCCIO_B14") (pintype "passive"))
    )
    (net (code "235") (name "TCK") (class "Default")
      (node (ref "JM1") (pin "90") (pinfunction "90_90") (pintype "bidirectional"))
      (node (ref "JTAG") (pin "6") (pinfunction "6_6") (pintype "passive"))
    )
    (net (code "236") (name "TDI") (class "Default")
      (node (ref "JM1") (pin "86") (pinfunction "86_86") (pintype "bidirectional"))
      (node (ref "JTAG") (pin "10") (pinfunction "10_10") (pintype "passive"))
    )
    (net (code "237") (name "TDO") (class "Default")
      (node (ref "JM1") (pin "88") (pinfunction "88_88") (pintype "bidirectional"))
      (node (ref "JTAG") (pin "8") (pinfunction "8_8") (pintype "passive"))
    )
    (net (code "238") (name "TMS") (class "Default")
      (node (ref "JM1") (pin "92") (pinfunction "92_92") (pintype "bidirectional"))
      (node (ref "JTAG") (pin "4") (pinfunction "4_4") (pintype "passive"))
    )
    (net (code "239") (name "VCCIO0") (class "Default")
      (node (ref "JM2") (pin "53") (pinfunction "53_53") (pintype "bidirectional"))
      (node (ref "JTAG") (pin "2") (pinfunction "2_2") (pintype "passive"))
    )
    (net (code "240") (name "VCCIO14") (class "Default")
      (node (ref "JM1") (pin "83") (pinfunction "83_83") (pintype "bidirectional"))
    )
    (net (code "241") (name "VCCO_4") (class "Default")
      (node (ref "C17") (pin "1") (pinfunction "1_1") (pintype "passive"))
      (node (ref "C18") (pin "1") (pinfunction "1_1") (pintype "passive"))
      (node (ref "C19") (pin "1") (pinfunction "1_1") (pintype "passive"))
      (node (ref "FB4") (pin "2") (pinfunction "2_2") (pintype "passive"))
      (node (ref "U3") (pin "24") (pinfunction "VCCO_1_24") (pintype "power_in"))
      (node (ref "U3") (pin "25") (pinfunction "VCCO_0_25") (pintype "power_in"))
    )
    (net (code "242") (name "VCCO_8") (class "Default")
      (node (ref "C35") (pin "1") (pinfunction "1_1") (pintype "passive"))
      (node (ref "C36") (pin "1") (pinfunction "1_1") (pintype "passive"))
      (node (ref "C37") (pin "1") (pinfunction "1_1") (pintype "passive"))
      (node (ref "FB7") (pin "2") (pinfunction "2_2") (pintype "passive"))
      (node (ref "U4") (pin "24") (pinfunction "VCCO_1_24") (pintype "power_in"))
      (node (ref "U4") (pin "25") (pinfunction "VCCO_0_25") (pintype "power_in"))
    )
    (net (code "243") (name "VCCO_9") (class "Default")
      (node (ref "C53") (pin "1") (pinfunction "1_1") (pintype "passive"))
      (node (ref "C54") (pin "1") (pinfunction "1_1") (pintype "passive"))
      (node (ref "C55") (pin "1") (pinfunction "1_1") (pintype "passive"))
      (node (ref "FB10") (pin "2") (pinfunction "2_2") (pintype "passive"))
      (node (ref "U5") (pin "24") (pinfunction "VCCO_1_24") (pintype "power_in"))
      (node (ref "U5") (pin "25") (pinfunction "VCCO_0_25") (pintype "power_in"))
    )
    (net (code "244") (name "VCC_4") (class "Default")
      (node (ref "C14") (pin "1") (pinfunction "1_1") (pintype "passive"))
      (node (ref "C15") (pin "1") (pinfunction "1_1") (pintype "passive"))
      (node (ref "C16") (pin "1") (pinfunction "1_1") (pintype "passive"))
      (node (ref "FB3") (pin "2") (pinfunction "2_2") (pintype "passive"))
      (node (ref "U3") (pin "35") (pinfunction "VCC_CORE_35") (pintype "power_in"))
      (node (ref "U3") (pin "4") (pinfunction "VCC_SDI_4") (pintype "power_in"))
    )
    (net (code "245") (name "VCC_8") (class "Default")
      (node (ref "C32") (pin "1") (pinfunction "1_1") (pintype "passive"))
      (node (ref "C33") (pin "1") (pinfunction "1_1") (pintype "passive"))
      (node (ref "C34") (pin "1") (pinfunction "1_1") (pintype "passive"))
      (node (ref "FB6") (pin "2") (pinfunction "2_2") (pintype "passive"))
      (node (ref "U4") (pin "35") (pinfunction "VCC_CORE_35") (pintype "power_in"))
      (node (ref "U4") (pin "4") (pinfunction "VCC_DDI_4") (pintype "power_in"))
    )
    (net (code "246") (name "VCC_9") (class "Default")
      (node (ref "C50") (pin "1") (pinfunction "1_1") (pintype "passive"))
      (node (ref "C51") (pin "1") (pinfunction "1_1") (pintype "passive"))
      (node (ref "C52") (pin "1") (pinfunction "1_1") (pintype "passive"))
      (node (ref "FB9") (pin "2") (pinfunction "2_2") (pintype "passive"))
      (node (ref "U5") (pin "35") (pinfunction "VCC_CORE_35") (pintype "power_in"))
      (node (ref "U5") (pin "4") (pinfunction "VCC_DDI_4") (pintype "power_in"))
    )
    (net (code "247") (name "VDD_4") (class "Default")
      (node (ref "C10") (pin "1") (pinfunction "1_1") (pintype "passive"))
      (node (ref "C11") (pin "1") (pinfunction "1_1") (pintype "passive"))
      (node (ref "C12") (pin "1") (pinfunction "1_1") (pintype "passive"))
      (node (ref "C13") (pin "1") (pinfunction "1_1") (pintype "passive"))
      (node (ref "FB2") (pin "2") (pinfunction "2_2") (pintype "passive"))
      (node (ref "U3") (pin "16") (pinfunction "VDD_16") (pintype "power_in"))
      (node (ref "U3") (pin "20") (pinfunction "VCCO1V8_1_20") (pintype "power_in"))
      (node (ref "U3") (pin "29") (pinfunction "VCCO1V8_0_29") (pintype "power_in"))
    )
    (net (code "248") (name "VDD_8") (class "Default")
      (node (ref "C28") (pin "1") (pinfunction "1_1") (pintype "passive"))
      (node (ref "C29") (pin "1") (pinfunction "1_1") (pintype "passive"))
      (node (ref "C30") (pin "1") (pinfunction "1_1") (pintype "passive"))
      (node (ref "C31") (pin "1") (pinfunction "1_1") (pintype "passive"))
      (node (ref "FB5") (pin "2") (pinfunction "2_2") (pintype "passive"))
      (node (ref "U4") (pin "16") (pinfunction "VDD_16") (pintype "power_in"))
      (node (ref "U4") (pin "20") (pinfunction "VCCO1V8_1_20") (pintype "power_in"))
      (node (ref "U4") (pin "29") (pinfunction "VCCO1V8_0_29") (pintype "power_in"))
    )
    (net (code "249") (name "VDD_9") (class "Default")
      (node (ref "C46") (pin "1") (pinfunction "1_1") (pintype "passive"))
      (node (ref "C47") (pin "1") (pinfunction "1_1") (pintype "passive"))
      (node (ref "C48") (pin "1") (pinfunction "1_1") (pintype "passive"))
      (node (ref "C49") (pin "1") (pinfunction "1_1") (pintype "passive"))
      (node (ref "FB8") (pin "2") (pinfunction "2_2") (pintype "passive"))
      (node (ref "U5") (pin "16") (pinfunction "VDD_16") (pintype "power_in"))
      (node (ref "U5") (pin "20") (pinfunction "VCCO1V8_1_20") (pintype "power_in"))
      (node (ref "U5") (pin "29") (pinfunction "VCCO1V8_0_29") (pintype "power_in"))
    )
    (net (code "250") (name "VOUT_A") (class "Default")
      (node (ref "C57") (pin "1") (pinfunction "1_1") (pintype "passive"))
      (node (ref "FB11") (pin "1") (pinfunction "1_1") (pintype "passive"))
      (node (ref "R17") (pin "2") (pinfunction "2_2") (pintype "passive"))
      (node (ref "U6") (pin "8") (pinfunction "VOUT_8") (pintype "output"))
    )
    (net (code "251") (name "VOUT_B") (class "Default")
      (node (ref "C59") (pin "1") (pinfunction "1_1") (pintype "passive"))
      (node (ref "FB12") (pin "1") (pinfunction "1_1") (pintype "passive"))
      (node (ref "R19") (pin "2") (pinfunction "2_2") (pintype "passive"))
      (node (ref "U7") (pin "8") (pinfunction "VOUT_8") (pintype "output"))
    )
    (net (code "252") (name "VSUP") (class "Default")
      (node (ref "C56") (pin "1") (pinfunction "1_1") (pintype "passive"))
      (node (ref "C58") (pin "1") (pinfunction "1_1") (pintype "passive"))
      (node (ref "JP2") (pin "2") (pinfunction "2_2") (pintype "passive"))
      (node (ref "R21") (pin "2") (pinfunction "2_2") (pintype "passive"))
      (node (ref "R99") (pin "2") (pinfunction "2_2") (pintype "passive"))
      (node (ref "U6") (pin "3") (pinfunction "VIN_3") (pintype "power_in"))
      (node (ref "U6") (pin "4") (pinfunction "VIN_4") (pintype "power_in"))
      (node (ref "U7") (pin "3") (pinfunction "VIN_3") (pintype "power_in"))
      (node (ref "U7") (pin "4") (pinfunction "VIN_4") (pintype "power_in"))
    )
    (net (code "253") (name "VXX") (class "Default")
      (node (ref "C1") (pin "1") (pinfunction "1_1") (pintype "passive"))
      (node (ref "FB1") (pin "2") (pinfunction "2_2") (pintype "passive"))
      (node (ref "U1") (pin "6") (pinfunction "VCC_6") (pintype "power_in"))
    )
    (net (code "254") (name "unconnected-(JTAG-Pad12)") (class "Default")
      (node (ref "JTAG") (pin "12") (pinfunction "12_12") (pintype "passive"))
    )
    (net (code "255") (name "unconnected-(JTAG-Pad14)") (class "Default")
      (node (ref "JTAG") (pin "14") (pinfunction "14_14") (pintype "passive"))
    )
    (net (code "256") (name "unconnected-(PCIE-NORTH-PWRGD-PadA11)") (class "Default")
      (node (ref "PCIE-NORTH") (pin "A11") (pinfunction "PWRGD_A11") (pintype "passive"))
    )
    (net (code "257") (name "unconnected-(PCIE-SOUTH-PWRGD-PadA11)") (class "Default")
      (node (ref "PCIE-SOUTH") (pin "A11") (pinfunction "PWRGD_A11") (pintype "passive"))
    )
    (net (code "258") (name "unconnected-(PCIE-SOUTH-SCL-PadB2)") (class "Default")
      (node (ref "PCIE-SOUTH") (pin "B2") (pinfunction "SCL_B2") (pintype "passive"))
    )
    (net (code "259") (name "unconnected-(PCIE-SOUTH-SDA-PadB1)") (class "Default")
      (node (ref "PCIE-SOUTH") (pin "B1") (pinfunction "SDA_B1") (pintype "passive"))
    )
    (net (code "260") (name "unconnected-(PCIE-SOUTH-V_I2C-PadB3)") (class "Default")
      (node (ref "PCIE-SOUTH") (pin "B3") (pinfunction "V_I2C_B3") (pintype "passive"))
    )
  )
)
